# Ind_current_sensor.net
KiCad netlist of a schematic drawn in Altium Designer
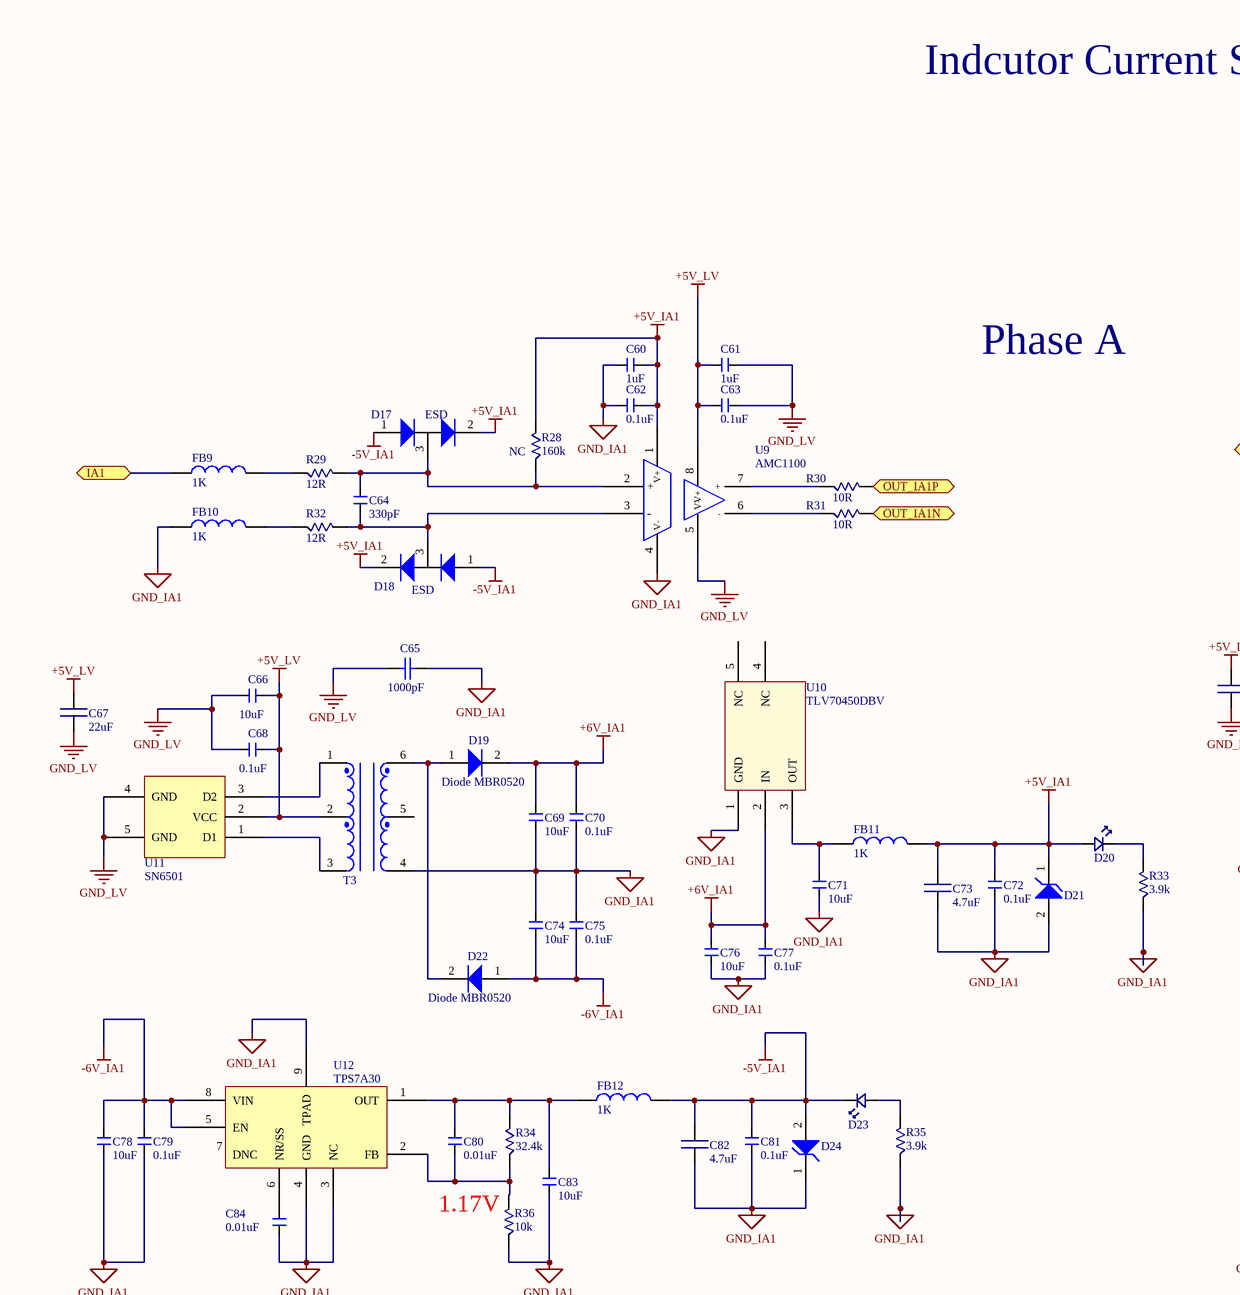
[diagram p0: Ind_current_sensor.SchDoc, top left]
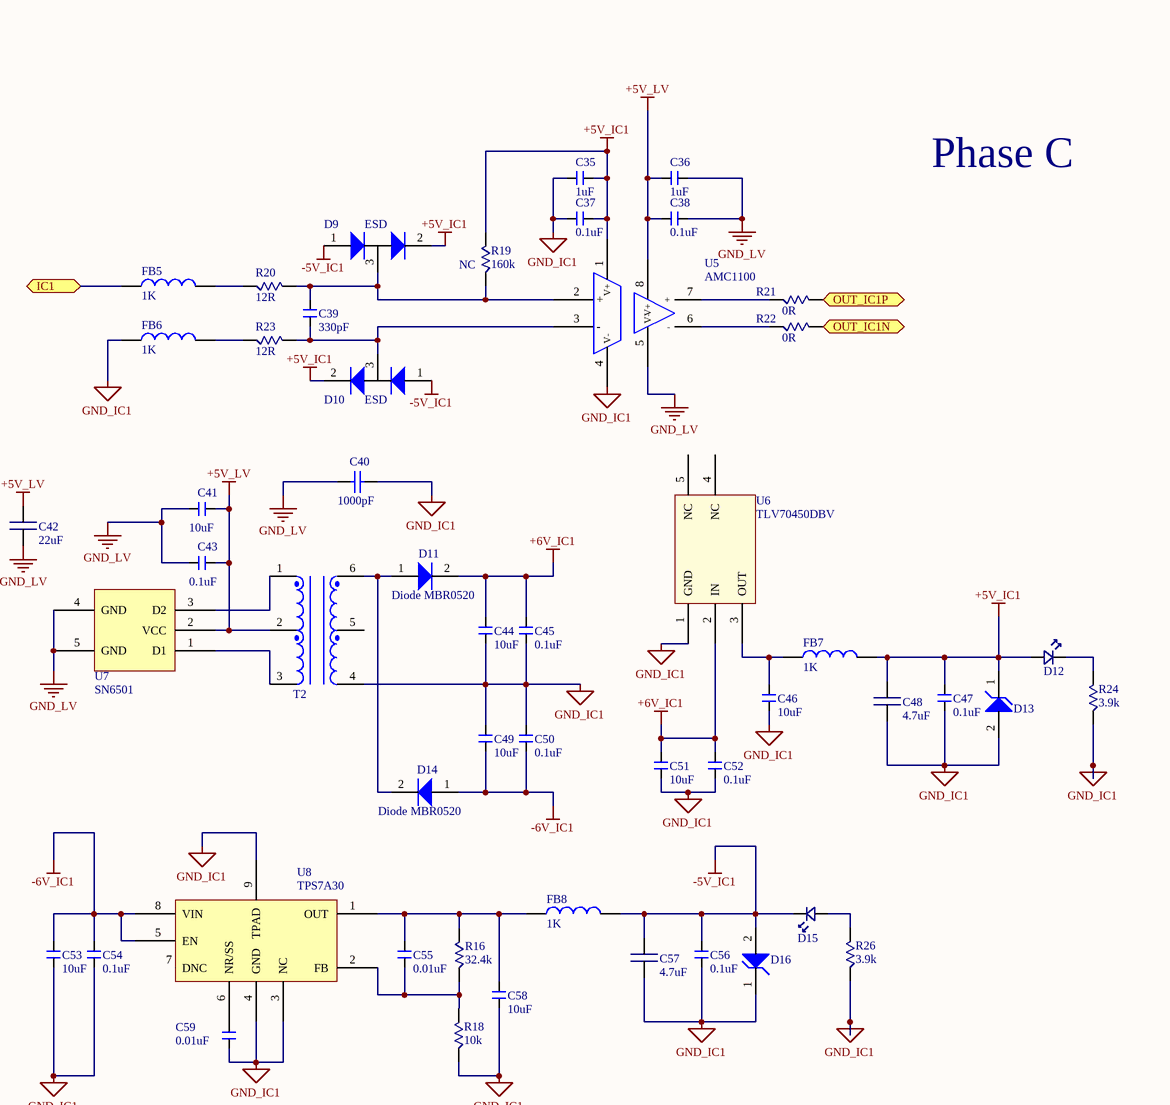
[diagram p1: Ind_current_sensor.SchDoc, top right]
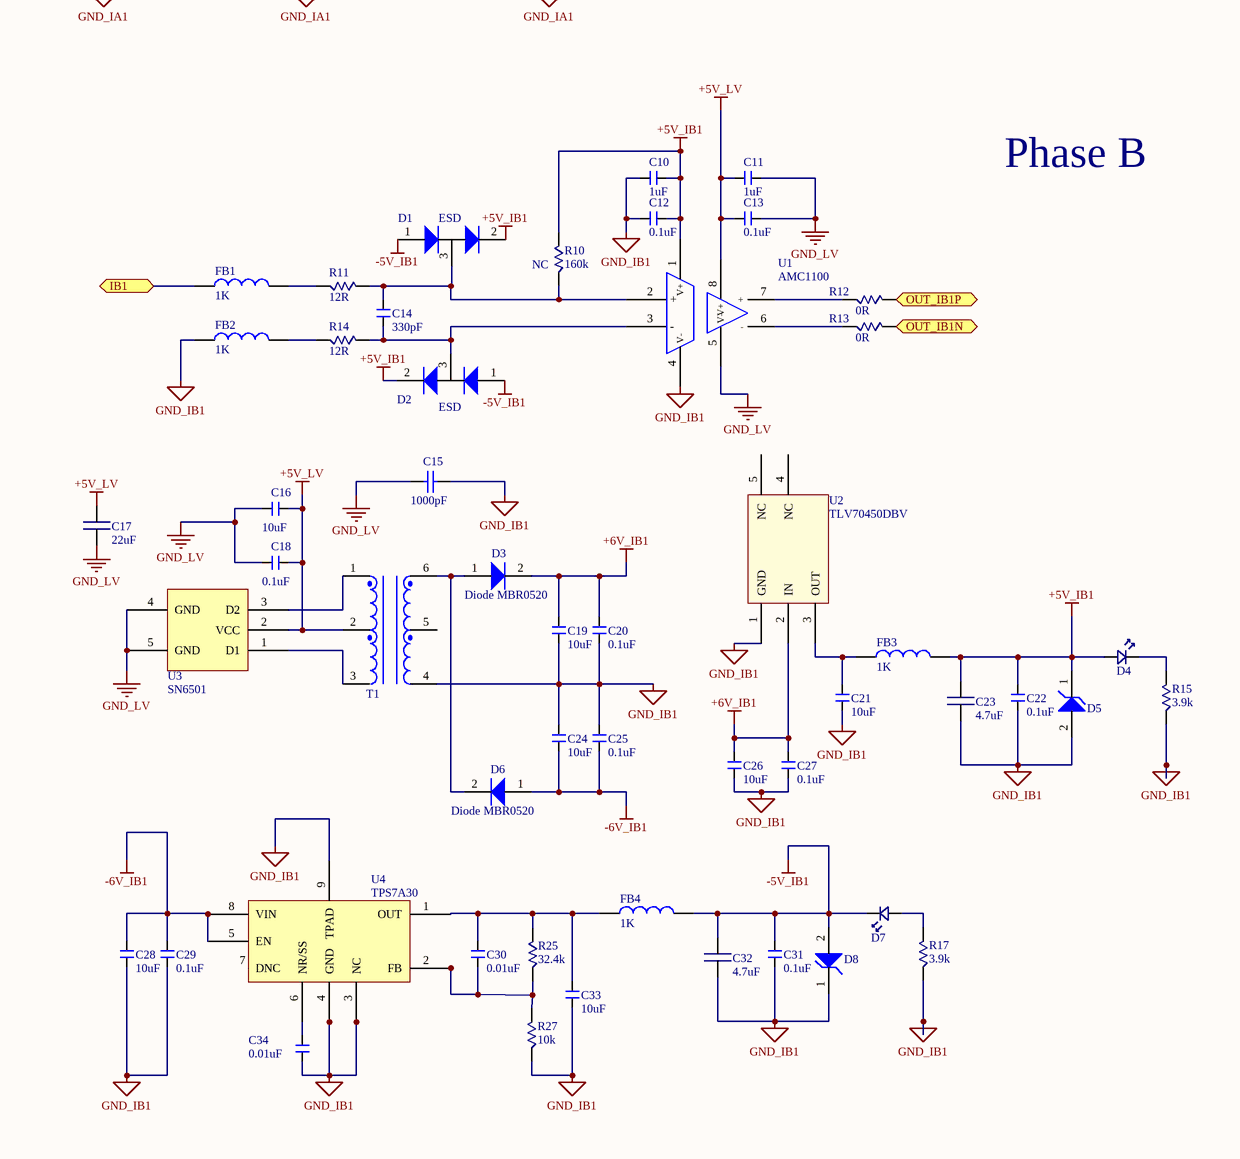
[diagram p2: Ind_current_sensor.SchDoc, bottom left]
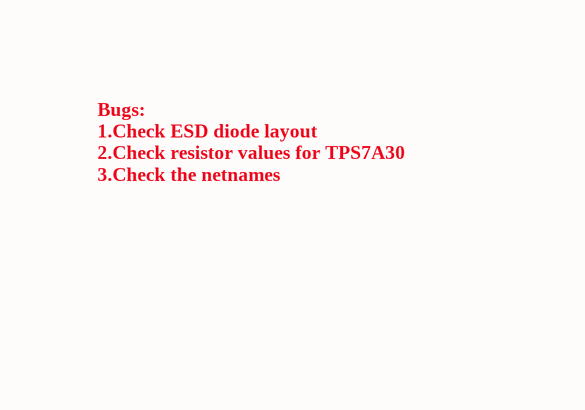
[diagram p3: Ind_current_sensor.SchDoc, bottom right]

(export (version "E")
  (design (tool "Eeschema 10.0.6"))
  (components
    (comp (ref "C10")
      (value "1uF")
      (footprint "0603 (1608 Metric)")
      (description "CAP CER 1UF 50V X5R 0603")
      (fields (field (name "PART") "1276-1860-1-ND") (field (name "Comment") "Cap 0603_new"))
      (libsource (lib "Library_Microgrid") (part "Cap 0603_new"))
    )
    (comp (ref "C11")
      (value "1uF")
      (footprint "0603 (1608 Metric)")
      (description "CAP CER 1UF 50V X5R 0603")
      (fields (field (name "PART") "1276-1860-1-ND") (field (name "Comment") "Cap 0603_new"))
      (libsource (lib "Library_Microgrid") (part "Cap 0603_new"))
    )
    (comp (ref "C12")
      (value "0.1uF")
      (footprint "0603 (1608 Metric)")
      (description "CAP CER 0.1UF 50V Y5V 0603")
      (fields (field (name "PART") "311-1343-6-ND") (field (name "Comment") "Cap 0603_new"))
      (libsource (lib "Library_Microgrid") (part "Cap 0603_new"))
    )
    (comp (ref "C13")
      (value "0.1uF")
      (footprint "0603 (1608 Metric)")
      (description "CAP CER 0.1UF 50V Y5V 0603")
      (fields (field (name "PART") "311-1343-6-ND") (field (name "Comment") "Cap 0603_new"))
      (libsource (lib "Library_Microgrid") (part "Cap 0603_new"))
    )
    (comp (ref "C14")
      (value "330pF")
      (footprint "0603 (1608 Metric)")
      (description "CAP CER 330PF 50V C0G 0603")
      (fields (field (name "PART") "445-7033-2-ND") (field (name "Comment") "Cap 0603_new"))
      (libsource (lib "Library_Microgrid") (part "Cap 0603_new"))
    )
    (comp (ref "C15")
      (value "1000pF")
      (footprint "RAD-0.3")
      (description "CAP CER 1000PF 1KV Y5P RADIAL")
      (fields
        (field (name "PART") "1251PH-ND")
        (field (name "Comment") "Cap TH")
        (field (name "PUBLISHER") "Altium Limited")
      )
      (libsource (lib "Miscellaneous Devices") (part "Cap"))
    )
    (comp (ref "C16")
      (value "10uF")
      (footprint "0603 (1608 Metric)")
      (description "CAP CER 10UF 35V X5R 0805")
      (fields (field (name "PART") "490-10515-1-ND") (field (name "Comment") "Cap 0603_new"))
      (libsource (lib "Library_Microgrid") (part "Cap 0603_new"))
    )
    (comp (ref "C17")
      (value "22uF")
      (footprint "0805 (2012 metric)")
      (description "CAP CER 22UF 35V X5R 0805")
      (fields (field (name "PART") "445-14428-1-ND") (field (name "Comment") "Cap 0805"))
      (libsource (lib "Library_Microgrid") (part "Cap 0805"))
    )
    (comp (ref "C18")
      (value "0.1uF")
      (footprint "0603 (1608 Metric)")
      (description "CAP CER 0.1UF 50V Y5V 0603")
      (fields (field (name "PART") "311-1343-6-ND") (field (name "Comment") "Cap 0603_new"))
      (libsource (lib "Library_Microgrid") (part "Cap 0603_new"))
    )
    (comp (ref "C19")
      (value "10uF")
      (footprint "0603 (1608 Metric)")
      (description "CAP CER 10UF 35V X5R 0805")
      (fields (field (name "PART") "490-10515-1-ND") (field (name "Comment") "Cap 0603_new"))
      (libsource (lib "Library_Microgrid") (part "Cap 0603_new"))
    )
    (comp (ref "C20")
      (value "0.1uF")
      (footprint "0603 (1608 Metric)")
      (description "CAP CER 0.1UF 50V Y5V 0603")
      (fields (field (name "PART") "311-1343-6-ND") (field (name "Comment") "Cap 0603_new"))
      (libsource (lib "Library_Microgrid") (part "Cap 0603_new"))
    )
    (comp (ref "C21")
      (value "10uF")
      (footprint "0603 (1608 Metric)")
      (description "CAP CER 10UF 35V X5R 0805")
      (fields (field (name "PART") "490-10515-1-ND") (field (name "Comment") "Cap 0603_new"))
      (libsource (lib "Library_Microgrid") (part "Cap 0603_new"))
    )
    (comp (ref "C22")
      (value "0.1uF")
      (footprint "0603 (1608 Metric)")
      (description "CAP CER 0.1UF 50V Y5V 0603")
      (fields (field (name "PART") "311-1343-6-ND") (field (name "Comment") "Cap 0603_new"))
      (libsource (lib "Library_Microgrid") (part "Cap 0603_new"))
    )
    (comp (ref "C23")
      (value "4.7uF")
      (footprint "0805 (2012 metric)")
      (description "CAP CER 4.7UF 50V X5R 0805")
      (fields (field (name "PART") "445-5980-1-ND") (field (name "Comment") "Cap 0805"))
      (libsource (lib "Library_Microgrid") (part "Cap 0805"))
    )
    (comp (ref "C24")
      (value "10uF")
      (footprint "0603 (1608 Metric)")
      (description "CAP CER 10UF 35V X5R 0805")
      (fields (field (name "PART") "490-10515-1-ND") (field (name "Comment") "Cap 0603_new"))
      (libsource (lib "Library_Microgrid") (part "Cap 0603_new"))
    )
    (comp (ref "C25")
      (value "0.1uF")
      (footprint "0603 (1608 Metric)")
      (description "CAP CER 0.1UF 50V Y5V 0603")
      (fields (field (name "PART") "311-1343-6-ND") (field (name "Comment") "Cap 0603_new"))
      (libsource (lib "Library_Microgrid") (part "Cap 0603_new"))
    )
    (comp (ref "C26")
      (value "10uF")
      (footprint "0603 (1608 Metric)")
      (description "CAP CER 10UF 35V X5R 0805")
      (fields (field (name "PART") "490-10515-1-ND") (field (name "Comment") "Cap 0603_new"))
      (libsource (lib "Library_Microgrid") (part "Cap 0603_new"))
    )
    (comp (ref "C27")
      (value "0.1uF")
      (footprint "0603 (1608 Metric)")
      (description "CAP CER 0.1UF 50V Y5V 0603")
      (fields (field (name "PART") "311-1343-6-ND") (field (name "Comment") "Cap 0603_new"))
      (libsource (lib "Library_Microgrid") (part "Cap 0603_new"))
    )
    (comp (ref "C28")
      (value "10uF")
      (footprint "0603 (1608 Metric)")
      (description "CAP CER 10UF 35V X5R 0805")
      (fields (field (name "PART") "490-10515-1-ND") (field (name "Comment") "Cap 0603_new"))
      (libsource (lib "Library_Microgrid") (part "Cap 0603_new"))
    )
    (comp (ref "C29")
      (value "0.1uF")
      (footprint "0603 (1608 Metric)")
      (description "CAP CER 0.1UF 50V Y5V 0603")
      (fields (field (name "PART") "311-1343-6-ND") (field (name "Comment") "Cap 0603_new"))
      (libsource (lib "Library_Microgrid") (part "Cap 0603_new"))
    )
    (comp (ref "C30")
      (value "0.01uF")
      (footprint "0603 (1608 Metric)")
      (description "CAP CER 10000PF 100V X7R 0603")
      (fields (field (name "PART") "478-7418-1-ND") (field (name "Comment") "Cap 0603_new"))
      (libsource (lib "Library_Microgrid") (part "Cap 0603_new"))
    )
    (comp (ref "C31")
      (value "0.1uF")
      (footprint "0603 (1608 Metric)")
      (description "CAP CER 0.1UF 50V Y5V 0603")
      (fields (field (name "PART") "311-1343-6-ND") (field (name "Comment") "Cap 0603_new"))
      (libsource (lib "Library_Microgrid") (part "Cap 0603_new"))
    )
    (comp (ref "C32")
      (value "4.7uF")
      (footprint "0805 (2012 metric)")
      (description "CAP CER 4.7UF 50V X5R 0805")
      (fields (field (name "PART") "445-5980-1-ND") (field (name "Comment") "Cap 0805"))
      (libsource (lib "Library_Microgrid") (part "Cap 0805"))
    )
    (comp (ref "C33")
      (value "10uF")
      (footprint "0603 (1608 Metric)")
      (description "CAP CER 10UF 35V X5R 0805")
      (fields (field (name "PART") "490-10515-1-ND") (field (name "Comment") "Cap 0603_new"))
      (libsource (lib "Library_Microgrid") (part "Cap 0603_new"))
    )
    (comp (ref "C34")
      (value "0.01uF")
      (footprint "0603 (1608 Metric)")
      (description "CAP CER 10000PF 100V X7R 0603")
      (fields (field (name "PART") "478-7418-1-ND") (field (name "Comment") "Cap 0603_new"))
      (libsource (lib "Library_Microgrid") (part "Cap 0603_new"))
    )
    (comp (ref "C35")
      (value "1uF")
      (footprint "0603 (1608 Metric)")
      (description "CAP CER 1UF 50V X5R 0603")
      (fields (field (name "PART") "1276-1860-1-ND") (field (name "Comment") "Cap 0603_new"))
      (libsource (lib "Library_Microgrid") (part "Cap 0603_new"))
    )
    (comp (ref "C36")
      (value "1uF")
      (footprint "0603 (1608 Metric)")
      (description "CAP CER 1UF 50V X5R 0603")
      (fields (field (name "PART") "1276-1860-1-ND") (field (name "Comment") "Cap 0603_new"))
      (libsource (lib "Library_Microgrid") (part "Cap 0603_new"))
    )
    (comp (ref "C37")
      (value "0.1uF")
      (footprint "0603 (1608 Metric)")
      (description "CAP CER 0.1UF 50V Y5V 0603")
      (fields (field (name "PART") "311-1343-6-ND") (field (name "Comment") "Cap 0603_new"))
      (libsource (lib "Library_Microgrid") (part "Cap 0603_new"))
    )
    (comp (ref "C38")
      (value "0.1uF")
      (footprint "0603 (1608 Metric)")
      (description "CAP CER 0.1UF 50V Y5V 0603")
      (fields (field (name "PART") "311-1343-6-ND") (field (name "Comment") "Cap 0603_new"))
      (libsource (lib "Library_Microgrid") (part "Cap 0603_new"))
    )
    (comp (ref "C39")
      (value "330pF")
      (footprint "0603 (1608 Metric)")
      (description "CAP CER 330PF 50V C0G 0603")
      (fields (field (name "PART") "445-7033-2-ND") (field (name "Comment") "Cap 0603_new"))
      (libsource (lib "Library_Microgrid") (part "Cap 0603_new"))
    )
    (comp (ref "C40")
      (value "1000pF")
      (footprint "RAD-0.3")
      (description "CAP CER 1000PF 1KV Y5P RADIAL")
      (fields
        (field (name "PART") "1251PH-ND")
        (field (name "Comment") "Cap TH")
        (field (name "PUBLISHER") "Altium Limited")
      )
      (libsource (lib "Miscellaneous Devices") (part "Cap"))
    )
    (comp (ref "C41")
      (value "10uF")
      (footprint "0603 (1608 Metric)")
      (description "CAP CER 10UF 35V X5R 0805")
      (fields (field (name "PART") "490-10515-1-ND") (field (name "Comment") "Cap 0603_new"))
      (libsource (lib "Library_Microgrid") (part "Cap 0603_new"))
    )
    (comp (ref "C42")
      (value "22uF")
      (footprint "0805 (2012 metric)")
      (description "CAP CER 22UF 35V X5R 0805")
      (fields (field (name "PART") "445-14428-1-ND") (field (name "Comment") "Cap 0805"))
      (libsource (lib "Library_Microgrid") (part "Cap 0805"))
    )
    (comp (ref "C43")
      (value "0.1uF")
      (footprint "0603 (1608 Metric)")
      (description "CAP CER 0.1UF 50V Y5V 0603")
      (fields (field (name "PART") "311-1343-6-ND") (field (name "Comment") "Cap 0603_new"))
      (libsource (lib "Library_Microgrid") (part "Cap 0603_new"))
    )
    (comp (ref "C44")
      (value "10uF")
      (footprint "0603 (1608 Metric)")
      (description "CAP CER 10UF 35V X5R 0805")
      (fields (field (name "PART") "490-10515-1-ND") (field (name "Comment") "Cap 0603_new"))
      (libsource (lib "Library_Microgrid") (part "Cap 0603_new"))
    )
    (comp (ref "C45")
      (value "0.1uF")
      (footprint "0603 (1608 Metric)")
      (description "CAP CER 0.1UF 50V Y5V 0603")
      (fields (field (name "PART") "311-1343-6-ND") (field (name "Comment") "Cap 0603_new"))
      (libsource (lib "Library_Microgrid") (part "Cap 0603_new"))
    )
    (comp (ref "C46")
      (value "10uF")
      (footprint "0603 (1608 Metric)")
      (description "CAP CER 10UF 35V X5R 0805")
      (fields (field (name "PART") "490-10515-1-ND") (field (name "Comment") "Cap 0603_new"))
      (libsource (lib "Library_Microgrid") (part "Cap 0603_new"))
    )
    (comp (ref "C47")
      (value "0.1uF")
      (footprint "0603 (1608 Metric)")
      (description "CAP CER 0.1UF 50V Y5V 0603")
      (fields (field (name "PART") "311-1343-6-ND") (field (name "Comment") "Cap 0603_new"))
      (libsource (lib "Library_Microgrid") (part "Cap 0603_new"))
    )
    (comp (ref "C48")
      (value "4.7uF")
      (footprint "0805 (2012 metric)")
      (description "CAP CER 4.7UF 50V X5R 0805")
      (fields (field (name "PART") "445-5980-1-ND") (field (name "Comment") "Cap 0805"))
      (libsource (lib "Library_Microgrid") (part "Cap 0805"))
    )
    (comp (ref "C49")
      (value "10uF")
      (footprint "0603 (1608 Metric)")
      (description "CAP CER 10UF 35V X5R 0805")
      (fields (field (name "PART") "490-10515-1-ND") (field (name "Comment") "Cap 0603_new"))
      (libsource (lib "Library_Microgrid") (part "Cap 0603_new"))
    )
    (comp (ref "C50")
      (value "0.1uF")
      (footprint "0603 (1608 Metric)")
      (description "CAP CER 0.1UF 50V Y5V 0603")
      (fields (field (name "PART") "311-1343-6-ND") (field (name "Comment") "Cap 0603_new"))
      (libsource (lib "Library_Microgrid") (part "Cap 0603_new"))
    )
    (comp (ref "C51")
      (value "10uF")
      (footprint "0603 (1608 Metric)")
      (description "CAP CER 10UF 35V X5R 0805")
      (fields (field (name "PART") "490-10515-1-ND") (field (name "Comment") "Cap 0603_new"))
      (libsource (lib "Library_Microgrid") (part "Cap 0603_new"))
    )
    (comp (ref "C52")
      (value "0.1uF")
      (footprint "0603 (1608 Metric)")
      (description "CAP CER 0.1UF 50V Y5V 0603")
      (fields (field (name "PART") "311-1343-6-ND") (field (name "Comment") "Cap 0603_new"))
      (libsource (lib "Library_Microgrid") (part "Cap 0603_new"))
    )
    (comp (ref "C53")
      (value "10uF")
      (footprint "0603 (1608 Metric)")
      (description "CAP CER 10UF 35V X5R 0805")
      (fields (field (name "PART") "490-10515-1-ND") (field (name "Comment") "Cap 0603_new"))
      (libsource (lib "Library_Microgrid") (part "Cap 0603_new"))
    )
    (comp (ref "C54")
      (value "0.1uF")
      (footprint "0603 (1608 Metric)")
      (description "CAP CER 0.1UF 50V Y5V 0603")
      (fields (field (name "PART") "311-1343-6-ND") (field (name "Comment") "Cap 0603_new"))
      (libsource (lib "Library_Microgrid") (part "Cap 0603_new"))
    )
    (comp (ref "C55")
      (value "0.01uF")
      (footprint "0603 (1608 Metric)")
      (description "CAP CER 10000PF 100V X7R 0603")
      (fields (field (name "PART") "478-7418-1-ND") (field (name "Comment") "Cap 0603_new"))
      (libsource (lib "Library_Microgrid") (part "Cap 0603_new"))
    )
    (comp (ref "C56")
      (value "0.1uF")
      (footprint "0603 (1608 Metric)")
      (description "CAP CER 0.1UF 50V Y5V 0603")
      (fields (field (name "PART") "311-1343-6-ND") (field (name "Comment") "Cap 0603_new"))
      (libsource (lib "Library_Microgrid") (part "Cap 0603_new"))
    )
    (comp (ref "C57")
      (value "4.7uF")
      (footprint "0805 (2012 metric)")
      (description "CAP CER 4.7UF 50V X5R 0805")
      (fields (field (name "PART") "445-5980-1-ND") (field (name "Comment") "Cap 0805"))
      (libsource (lib "Library_Microgrid") (part "Cap 0805"))
    )
    (comp (ref "C58")
      (value "10uF")
      (footprint "0603 (1608 Metric)")
      (description "CAP CER 10UF 35V X5R 0805")
      (fields (field (name "PART") "490-10515-1-ND") (field (name "Comment") "Cap 0603_new"))
      (libsource (lib "Library_Microgrid") (part "Cap 0603_new"))
    )
    (comp (ref "C59")
      (value "0.01uF")
      (footprint "0603 (1608 Metric)")
      (description "CAP CER 10000PF 100V X7R 0603")
      (fields (field (name "PART") "478-7418-1-ND") (field (name "Comment") "Cap 0603_new"))
      (libsource (lib "Library_Microgrid") (part "Cap 0603_new"))
    )
    (comp (ref "C60")
      (value "1uF")
      (footprint "0603 (1608 Metric)")
      (description "CAP CER 1UF 50V X5R 0603")
      (fields (field (name "PART") "1276-1860-1-ND") (field (name "Comment") "Cap 0603_new"))
      (libsource (lib "Library_Microgrid") (part "Cap 0603_new"))
    )
    (comp (ref "C61")
      (value "1uF")
      (footprint "0603 (1608 Metric)")
      (description "CAP CER 1UF 50V X5R 0603")
      (fields (field (name "PART") "1276-1860-1-ND") (field (name "Comment") "Cap 0603_new"))
      (libsource (lib "Library_Microgrid") (part "Cap 0603_new"))
    )
    (comp (ref "C62")
      (value "0.1uF")
      (footprint "0603 (1608 Metric)")
      (description "CAP CER 0.1UF 50V Y5V 0603")
      (fields (field (name "PART") "311-1343-6-ND") (field (name "Comment") "Cap 0603_new"))
      (libsource (lib "Library_Microgrid") (part "Cap 0603_new"))
    )
    (comp (ref "C63")
      (value "0.1uF")
      (footprint "0603 (1608 Metric)")
      (description "CAP CER 0.1UF 50V Y5V 0603")
      (fields (field (name "PART") "311-1343-6-ND") (field (name "Comment") "Cap 0603_new"))
      (libsource (lib "Library_Microgrid") (part "Cap 0603_new"))
    )
    (comp (ref "C64")
      (value "330pF")
      (footprint "0603 (1608 Metric)")
      (description "CAP CER 330PF 50V C0G 0603")
      (fields (field (name "PART") "445-7033-2-ND") (field (name "Comment") "Cap 0603_new"))
      (libsource (lib "Library_Microgrid") (part "Cap 0603_new"))
    )
    (comp (ref "C65")
      (value "1000pF")
      (footprint "RAD-0.3")
      (description "CAP CER 1000PF 1KV Y5P RADIAL")
      (fields
        (field (name "PART") "1251PH-ND")
        (field (name "Comment") "Cap TH")
        (field (name "PUBLISHER") "Altium Limited")
      )
      (libsource (lib "Miscellaneous Devices") (part "Cap"))
    )
    (comp (ref "C66")
      (value "10uF")
      (footprint "0603 (1608 Metric)")
      (description "CAP CER 10UF 35V X5R 0805")
      (fields (field (name "PART") "490-10515-1-ND") (field (name "Comment") "Cap 0603_new"))
      (libsource (lib "Library_Microgrid") (part "Cap 0603_new"))
    )
    (comp (ref "C67")
      (value "22uF")
      (footprint "0805 (2012 metric)")
      (description "CAP CER 22UF 35V X5R 0805")
      (fields (field (name "PART") "445-14428-1-ND") (field (name "Comment") "Cap 0805"))
      (libsource (lib "Library_Microgrid") (part "Cap 0805"))
    )
    (comp (ref "C68")
      (value "0.1uF")
      (footprint "0603 (1608 Metric)")
      (description "CAP CER 0.1UF 50V Y5V 0603")
      (fields (field (name "PART") "311-1343-6-ND") (field (name "Comment") "Cap 0603_new"))
      (libsource (lib "Library_Microgrid") (part "Cap 0603_new"))
    )
    (comp (ref "C69")
      (value "10uF")
      (footprint "0603 (1608 Metric)")
      (description "CAP CER 10UF 35V X5R 0805")
      (fields (field (name "PART") "490-10515-1-ND") (field (name "Comment") "Cap 0603_new"))
      (libsource (lib "Library_Microgrid") (part "Cap 0603_new"))
    )
    (comp (ref "C70")
      (value "0.1uF")
      (footprint "0603 (1608 Metric)")
      (description "CAP CER 0.1UF 50V Y5V 0603")
      (fields (field (name "PART") "311-1343-6-ND") (field (name "Comment") "Cap 0603_new"))
      (libsource (lib "Library_Microgrid") (part "Cap 0603_new"))
    )
    (comp (ref "C71")
      (value "10uF")
      (footprint "0603 (1608 Metric)")
      (description "CAP CER 10UF 35V X5R 0805")
      (fields (field (name "PART") "490-10515-1-ND") (field (name "Comment") "Cap 0603_new"))
      (libsource (lib "Library_Microgrid") (part "Cap 0603_new"))
    )
    (comp (ref "C72")
      (value "0.1uF")
      (footprint "0603 (1608 Metric)")
      (description "CAP CER 0.1UF 50V Y5V 0603")
      (fields (field (name "PART") "311-1343-6-ND") (field (name "Comment") "Cap 0603_new"))
      (libsource (lib "Library_Microgrid") (part "Cap 0603_new"))
    )
    (comp (ref "C73")
      (value "4.7uF")
      (footprint "0805 (2012 metric)")
      (description "CAP CER 4.7UF 50V X5R 0805")
      (fields (field (name "PART") "445-5980-1-ND") (field (name "Comment") "Cap 0805"))
      (libsource (lib "Library_Microgrid") (part "Cap 0805"))
    )
    (comp (ref "C74")
      (value "10uF")
      (footprint "0603 (1608 Metric)")
      (description "CAP CER 10UF 35V X5R 0805")
      (fields (field (name "PART") "490-10515-1-ND") (field (name "Comment") "Cap 0603_new"))
      (libsource (lib "Library_Microgrid") (part "Cap 0603_new"))
    )
    (comp (ref "C75")
      (value "0.1uF")
      (footprint "0603 (1608 Metric)")
      (description "CAP CER 0.1UF 50V Y5V 0603")
      (fields (field (name "PART") "311-1343-6-ND") (field (name "Comment") "Cap 0603_new"))
      (libsource (lib "Library_Microgrid") (part "Cap 0603_new"))
    )
    (comp (ref "C76")
      (value "10uF")
      (footprint "0603 (1608 Metric)")
      (description "CAP CER 10UF 35V X5R 0805")
      (fields (field (name "PART") "490-10515-1-ND") (field (name "Comment") "Cap 0603_new"))
      (libsource (lib "Library_Microgrid") (part "Cap 0603_new"))
    )
    (comp (ref "C77")
      (value "0.1uF")
      (footprint "0603 (1608 Metric)")
      (description "CAP CER 0.1UF 50V Y5V 0603")
      (fields (field (name "PART") "311-1343-6-ND") (field (name "Comment") "Cap 0603_new"))
      (libsource (lib "Library_Microgrid") (part "Cap 0603_new"))
    )
    (comp (ref "C78")
      (value "10uF")
      (footprint "0603 (1608 Metric)")
      (description "CAP CER 10UF 35V X5R 0805")
      (fields (field (name "PART") "490-10515-1-ND") (field (name "Comment") "Cap 0603_new"))
      (libsource (lib "Library_Microgrid") (part "Cap 0603_new"))
    )
    (comp (ref "C79")
      (value "0.1uF")
      (footprint "0603 (1608 Metric)")
      (description "CAP CER 0.1UF 50V Y5V 0603")
      (fields (field (name "PART") "311-1343-6-ND") (field (name "Comment") "Cap 0603_new"))
      (libsource (lib "Library_Microgrid") (part "Cap 0603_new"))
    )
    (comp (ref "C80")
      (value "0.01uF")
      (footprint "0603 (1608 Metric)")
      (description "CAP CER 10000PF 100V X7R 0603")
      (fields (field (name "PART") "478-7418-1-ND") (field (name "Comment") "Cap 0603_new"))
      (libsource (lib "Library_Microgrid") (part "Cap 0603_new"))
    )
    (comp (ref "C81")
      (value "0.1uF")
      (footprint "0603 (1608 Metric)")
      (description "CAP CER 0.1UF 50V Y5V 0603")
      (fields (field (name "PART") "311-1343-6-ND") (field (name "Comment") "Cap 0603_new"))
      (libsource (lib "Library_Microgrid") (part "Cap 0603_new"))
    )
    (comp (ref "C82")
      (value "4.7uF")
      (footprint "0805 (2012 metric)")
      (description "CAP CER 4.7UF 50V X5R 0805")
      (fields (field (name "PART") "445-5980-1-ND") (field (name "Comment") "Cap 0805"))
      (libsource (lib "Library_Microgrid") (part "Cap 0805"))
    )
    (comp (ref "C83")
      (value "10uF")
      (footprint "0603 (1608 Metric)")
      (description "CAP CER 10UF 35V X5R 0805")
      (fields (field (name "PART") "490-10515-1-ND") (field (name "Comment") "Cap 0603_new"))
      (libsource (lib "Library_Microgrid") (part "Cap 0603_new"))
    )
    (comp (ref "C84")
      (value "0.01uF")
      (footprint "0603 (1608 Metric)")
      (description "CAP CER 10000PF 100V X7R 0603")
      (fields (field (name "PART") "478-7418-1-ND") (field (name "Comment") "Cap 0603_new"))
      (libsource (lib "Library_Microgrid") (part "Cap 0603_new"))
    )
    (comp (ref "D1")
      (value "ESD")
      (footprint "SOT323_ESD")
      (description "TVS DIODE")
      (fields (field (name "PART") "ESD1P0RFWH6327XTSA1CT") (field (name "Comment") "TVS - Diodes"))
      (libsource (lib "Library_Microgrid") (part "Diode_ESD"))
    )
    (comp (ref "D2")
      (value "ESD")
      (footprint "SOT323_ESD")
      (description "TVS DIODE")
      (fields (field (name "PART") "ESD1P0RFWH6327XTSA1CT") (field (name "Comment") "TVS - Diodes"))
      (libsource (lib "Library_Microgrid") (part "Diode_ESD"))
    )
    (comp (ref "D3")
      (value "Diode MBR0520")
      (footprint "SOD-123")
      (description "DIODE SCHOTTKY 20V 500MA SOD123")
      (fields (field (name "PART") "MBR0520LT1GOSCT-ND"))
      (libsource (lib "Library_Microgrid") (part "Diode MBR0520"))
    )
    (comp (ref "D4")
      (value "LED")
      (footprint "0805 (2012 Metric) Diode")
      (description "LED 0805")
      (libsource (lib "Library_Microgrid") (part "LED"))
    )
    (comp (ref "D5")
      (value "Diode Zener POWERDI123")
      (footprint "POWERDI")
      (description "DIODE ZENER POWERDI123")
      (fields (field (name "PART") "DFLZ6V2DICT-ND"))
      (libsource (lib "Library_Microgrid") (part "Diode Zener POWERDI123"))
    )
    (comp (ref "D6")
      (value "Diode MBR0520")
      (footprint "SOD-123")
      (description "DIODE SCHOTTKY 20V 500MA SOD123")
      (fields (field (name "PART") "MBR0520LT1GOSCT-ND"))
      (libsource (lib "Library_Microgrid") (part "Diode MBR0520"))
    )
    (comp (ref "D7")
      (value "LED")
      (footprint "0805 (2012 Metric) Diode")
      (description "LED 0805")
      (libsource (lib "Library_Microgrid") (part "LED"))
    )
    (comp (ref "D8")
      (value "Diode Zener POWERDI123")
      (footprint "POWERDI")
      (description "DIODE ZENER POWERDI123")
      (fields (field (name "PART") "DFLZ6V2DICT-ND"))
      (libsource (lib "Library_Microgrid") (part "Diode Zener POWERDI123"))
    )
    (comp (ref "D9")
      (value "ESD")
      (footprint "SOT323_ESD")
      (description "TVS DIODE")
      (fields (field (name "PART") "ESD1P0RFWH6327XTSA1CT") (field (name "Comment") "TVS - Diodes"))
      (libsource (lib "Library_Microgrid") (part "Diode_ESD"))
    )
    (comp (ref "D10")
      (value "ESD")
      (footprint "SOT323_ESD")
      (description "TVS DIODE")
      (fields (field (name "PART") "ESD1P0RFWH6327XTSA1CT") (field (name "Comment") "TVS - Diodes"))
      (libsource (lib "Library_Microgrid") (part "Diode_ESD"))
    )
    (comp (ref "D11")
      (value "Diode MBR0520")
      (footprint "SOD-123")
      (description "DIODE SCHOTTKY 20V 500MA SOD123")
      (fields (field (name "PART") "MBR0520LT1GOSCT-ND"))
      (libsource (lib "Library_Microgrid") (part "Diode MBR0520"))
    )
    (comp (ref "D12")
      (value "LED")
      (footprint "0805 (2012 Metric) Diode")
      (description "LED 0805")
      (libsource (lib "Library_Microgrid") (part "LED"))
    )
    (comp (ref "D13")
      (value "Diode Zener POWERDI123")
      (footprint "POWERDI")
      (description "DIODE ZENER POWERDI123")
      (fields (field (name "PART") "DFLZ6V2DICT-ND"))
      (libsource (lib "Library_Microgrid") (part "Diode Zener POWERDI123"))
    )
    (comp (ref "D14")
      (value "Diode MBR0520")
      (footprint "SOD-123")
      (description "DIODE SCHOTTKY 20V 500MA SOD123")
      (fields (field (name "PART") "MBR0520LT1GOSCT-ND"))
      (libsource (lib "Library_Microgrid") (part "Diode MBR0520"))
    )
    (comp (ref "D15")
      (value "LED")
      (footprint "0805 (2012 Metric) Diode")
      (description "LED 0805")
      (libsource (lib "Library_Microgrid") (part "LED"))
    )
    (comp (ref "D16")
      (value "Diode Zener POWERDI123")
      (footprint "POWERDI")
      (description "DIODE ZENER POWERDI123")
      (fields (field (name "PART") "DFLZ6V2DICT-ND"))
      (libsource (lib "Library_Microgrid") (part "Diode Zener POWERDI123"))
    )
    (comp (ref "D17")
      (value "ESD")
      (footprint "SOT323_ESD")
      (description "TVS DIODE")
      (fields (field (name "PART") "ESD1P0RFWH6327XTSA1CT") (field (name "Comment") "TVS - Diodes"))
      (libsource (lib "Library_Microgrid") (part "Diode_ESD"))
    )
    (comp (ref "D18")
      (value "ESD")
      (footprint "SOT323_ESD")
      (description "TVS DIODE")
      (fields (field (name "PART") "ESD1P0RFWH6327XTSA1CT") (field (name "Comment") "TVS - Diodes"))
      (libsource (lib "Library_Microgrid") (part "Diode_ESD"))
    )
    (comp (ref "D19")
      (value "Diode MBR0520")
      (footprint "SOD-123")
      (description "DIODE SCHOTTKY 20V 500MA SOD123")
      (fields (field (name "PART") "MBR0520LT1GOSCT-ND"))
      (libsource (lib "Library_Microgrid") (part "Diode MBR0520"))
    )
    (comp (ref "D20")
      (value "LED")
      (footprint "0805 (2012 Metric) Diode")
      (description "LED 0805")
      (libsource (lib "Library_Microgrid") (part "LED"))
    )
    (comp (ref "D21")
      (value "Diode Zener POWERDI123")
      (footprint "POWERDI")
      (description "DIODE ZENER POWERDI123")
      (fields (field (name "PART") "DFLZ6V2DICT-ND"))
      (libsource (lib "Library_Microgrid") (part "Diode Zener POWERDI123"))
    )
    (comp (ref "D22")
      (value "Diode MBR0520")
      (footprint "SOD-123")
      (description "DIODE SCHOTTKY 20V 500MA SOD123")
      (fields (field (name "PART") "MBR0520LT1GOSCT-ND"))
      (libsource (lib "Library_Microgrid") (part "Diode MBR0520"))
    )
    (comp (ref "D23")
      (value "LED")
      (footprint "0805 (2012 Metric) Diode")
      (description "LED 0805")
      (libsource (lib "Library_Microgrid") (part "LED"))
    )
    (comp (ref "D24")
      (value "Diode Zener POWERDI123")
      (footprint "POWERDI")
      (description "DIODE ZENER POWERDI123")
      (fields (field (name "PART") "DFLZ6V2DICT-ND"))
      (libsource (lib "Library_Microgrid") (part "Diode Zener POWERDI123"))
    )
    (comp (ref "FB1")
      (value "1K")
      (footprint "0603 (1608 Metric)")
      (description "FERRITE BEAD 1 KOHM 0603 1LN")
      (fields (field (name "PART") "445-8672-1-ND") (field (name "Comment") "Ferrite bead"))
      (libsource (lib "Library_Microgrid") (part "Ferrite bead"))
    )
    (comp (ref "FB2")
      (value "1K")
      (footprint "0603 (1608 Metric)")
      (description "FERRITE BEAD 1 KOHM 0603 1LN")
      (fields (field (name "PART") "445-8672-1-ND") (field (name "Comment") "Ferrite bead"))
      (libsource (lib "Library_Microgrid") (part "Ferrite bead"))
    )
    (comp (ref "FB3")
      (value "1K")
      (footprint "0603 (1608 Metric)")
      (description "FERRITE BEAD 1 KOHM 0603 1LN")
      (fields (field (name "PART") "445-8672-1-ND") (field (name "Comment") "Ferrite bead"))
      (libsource (lib "Library_Microgrid") (part "Ferrite bead"))
    )
    (comp (ref "FB4")
      (value "1K")
      (footprint "0603 (1608 Metric)")
      (description "FERRITE BEAD 1 KOHM 0603 1LN")
      (fields (field (name "PART") "445-8672-1-ND") (field (name "Comment") "Ferrite bead"))
      (libsource (lib "Library_Microgrid") (part "Ferrite bead"))
    )
    (comp (ref "FB5")
      (value "1K")
      (footprint "0603 (1608 Metric)")
      (description "FERRITE BEAD 1 KOHM 0603 1LN")
      (fields (field (name "PART") "445-8672-1-ND") (field (name "Comment") "Ferrite bead"))
      (libsource (lib "Library_Microgrid") (part "Ferrite bead"))
    )
    (comp (ref "FB6")
      (value "1K")
      (footprint "0603 (1608 Metric)")
      (description "FERRITE BEAD 1 KOHM 0603 1LN")
      (fields (field (name "PART") "445-8672-1-ND") (field (name "Comment") "Ferrite bead"))
      (libsource (lib "Library_Microgrid") (part "Ferrite bead"))
    )
    (comp (ref "FB7")
      (value "1K")
      (footprint "0603 (1608 Metric)")
      (description "FERRITE BEAD 1 KOHM 0603 1LN")
      (fields (field (name "PART") "445-8672-1-ND") (field (name "Comment") "Ferrite bead"))
      (libsource (lib "Library_Microgrid") (part "Ferrite bead"))
    )
    (comp (ref "FB8")
      (value "1K")
      (footprint "0603 (1608 Metric)")
      (description "FERRITE BEAD 1 KOHM 0603 1LN")
      (fields (field (name "PART") "445-8672-1-ND") (field (name "Comment") "Ferrite bead"))
      (libsource (lib "Library_Microgrid") (part "Ferrite bead"))
    )
    (comp (ref "FB9")
      (value "1K")
      (footprint "0603 (1608 Metric)")
      (description "FERRITE BEAD 1 KOHM 0603 1LN")
      (fields (field (name "PART") "445-8672-1-ND") (field (name "Comment") "Ferrite bead"))
      (libsource (lib "Library_Microgrid") (part "Ferrite bead"))
    )
    (comp (ref "FB10")
      (value "1K")
      (footprint "0603 (1608 Metric)")
      (description "FERRITE BEAD 1 KOHM 0603 1LN")
      (fields (field (name "PART") "445-8672-1-ND") (field (name "Comment") "Ferrite bead"))
      (libsource (lib "Library_Microgrid") (part "Ferrite bead"))
    )
    (comp (ref "FB11")
      (value "1K")
      (footprint "0603 (1608 Metric)")
      (description "FERRITE BEAD 1 KOHM 0603 1LN")
      (fields (field (name "PART") "445-8672-1-ND") (field (name "Comment") "Ferrite bead"))
      (libsource (lib "Library_Microgrid") (part "Ferrite bead"))
    )
    (comp (ref "FB12")
      (value "1K")
      (footprint "0603 (1608 Metric)")
      (description "FERRITE BEAD 1 KOHM 0603 1LN")
      (fields (field (name "PART") "445-8672-1-ND") (field (name "Comment") "Ferrite bead"))
      (libsource (lib "Library_Microgrid") (part "Ferrite bead"))
    )
    (comp (ref "R10")
      (value "NC")
      (footprint "0603 (1608 Metric)")
      (description "Resistor 0603")
      (fields (field (name "ALTIUM_VALUE") "160k"))
      (libsource (lib "Library_Microgrid") (part "Resistor 0603"))
    )
    (comp (ref "R11")
      (value "12R")
      (footprint "1206")
      (description "12 Ohm ±0.5% 0.25W, 1/4W Chip Resistor 1206")
      (fields (field (name "PART") "311-2961-1-ND") (field (name "Comment") "Resistor 1206"))
      (libsource (lib "Library_Microgrid") (part "Resistor 1206"))
    )
    (comp (ref "R12")
      (value "0R")
      (footprint "0603 (1608 Metric)")
      (description "RES SMD 10 OHM 0.05% 1/10W 0603")
      (fields (field (name "PART") "RNCF0603AKT10R0CT-ND") (field (name "Comment") "Resistor 0603"))
      (libsource (lib "Library_Microgrid") (part "Resistor 0603"))
    )
    (comp (ref "R13")
      (value "0R")
      (footprint "0603 (1608 Metric)")
      (description "RES SMD 10 OHM 0.05% 1/10W 0603")
      (fields (field (name "PART") "RNCF0603AKT10R0CT-ND") (field (name "Comment") "Resistor 0603"))
      (libsource (lib "Library_Microgrid") (part "Resistor 0603"))
    )
    (comp (ref "R14")
      (value "12R")
      (footprint "1206")
      (description "12 Ohm ±0.5% 0.25W, 1/4W Chip Resistor 1206")
      (fields (field (name "PART") "311-2961-1-ND") (field (name "Comment") "Resistor 1206"))
      (libsource (lib "Library_Microgrid") (part "Resistor 1206"))
    )
    (comp (ref "R15")
      (value "3.9k")
      (footprint "0603 (1608 Metric)")
      (description "RES SMD 3.9K OHM 5% 1/10W 0603")
      (fields (field (name "PART") "541-3.9KGCT-ND") (field (name "Comment") "Resistor 0603"))
      (libsource (lib "Library_Microgrid") (part "Resistor 0603"))
    )
    (comp (ref "R16")
      (value "32.4k")
      (footprint "0603 (1608 Metric)")
      (description "RES SMD 32.4KOHM 0.5% 1/10W 0603")
      (fields (field (name "PART") "311-32.4KDCT-ND") (field (name "Comment") "Resistor 0603"))
      (libsource (lib "Library_Microgrid") (part "Resistor 0603"))
    )
    (comp (ref "R17")
      (value "3.9k")
      (footprint "0603 (1608 Metric)")
      (description "RES SMD 3.9K OHM 5% 1/10W 0603")
      (fields (field (name "PART") "541-3.9KGCT-ND") (field (name "Comment") "Resistor 0603"))
      (libsource (lib "Library_Microgrid") (part "Resistor 0603"))
    )
    (comp (ref "R18")
      (value "10k")
      (footprint "0603 (1608 Metric)")
      (description "RES SMD 10K OHM 0.5% 1/16W 0603")
      (fields (field (name "PART") "RR08P10.0KDCT-ND") (field (name "Comment") "Resistor 0603"))
      (libsource (lib "Library_Microgrid") (part "Resistor 0603"))
    )
    (comp (ref "R19")
      (value "NC")
      (footprint "0603 (1608 Metric)")
      (description "Resistor 0603")
      (fields (field (name "ALTIUM_VALUE") "160k"))
      (libsource (lib "Library_Microgrid") (part "Resistor 0603"))
    )
    (comp (ref "R20")
      (value "12R")
      (footprint "1206")
      (description "12 Ohm ±0.5% 0.25W, 1/4W Chip Resistor 1206")
      (fields (field (name "PART") "311-2961-1-ND") (field (name "Comment") "Resistor 1206"))
      (libsource (lib "Library_Microgrid") (part "Resistor 1206"))
    )
    (comp (ref "R21")
      (value "0R")
      (footprint "0603 (1608 Metric)")
      (description "RES SMD 10 OHM 0.05% 1/10W 0603")
      (fields (field (name "PART") "RNCF0603AKT10R0CT-ND") (field (name "Comment") "Resistor 0603"))
      (libsource (lib "Library_Microgrid") (part "Resistor 0603"))
    )
    (comp (ref "R22")
      (value "0R")
      (footprint "0603 (1608 Metric)")
      (description "RES SMD 10 OHM 0.05% 1/10W 0603")
      (fields (field (name "PART") "RNCF0603AKT10R0CT-ND") (field (name "Comment") "Resistor 0603"))
      (libsource (lib "Library_Microgrid") (part "Resistor 0603"))
    )
    (comp (ref "R23")
      (value "12R")
      (footprint "1206")
      (description "12 Ohm ±0.5% 0.25W, 1/4W Chip Resistor 1206")
      (fields (field (name "PART") "311-2961-1-ND") (field (name "Comment") "Resistor 1206"))
      (libsource (lib "Library_Microgrid") (part "Resistor 1206"))
    )
    (comp (ref "R24")
      (value "3.9k")
      (footprint "0603 (1608 Metric)")
      (description "RES SMD 3.9K OHM 5% 1/10W 0603")
      (fields (field (name "PART") "541-3.9KGCT-ND") (field (name "Comment") "Resistor 0603"))
      (libsource (lib "Library_Microgrid") (part "Resistor 0603"))
    )
    (comp (ref "R25")
      (value "32.4k")
      (footprint "0603 (1608 Metric)")
      (description "RES SMD 32.4KOHM 0.5% 1/10W 0603")
      (fields (field (name "PART") "311-32.4KDCT-ND") (field (name "Comment") "Resistor 0603"))
      (libsource (lib "Library_Microgrid") (part "Resistor 0603"))
    )
    (comp (ref "R26")
      (value "3.9k")
      (footprint "0603 (1608 Metric)")
      (description "RES SMD 3.9K OHM 5% 1/10W 0603")
      (fields (field (name "PART") "541-3.9KGCT-ND") (field (name "Comment") "Resistor 0603"))
      (libsource (lib "Library_Microgrid") (part "Resistor 0603"))
    )
    (comp (ref "R27")
      (value "10k")
      (footprint "0603 (1608 Metric)")
      (description "RES SMD 10K OHM 0.5% 1/16W 0603")
      (fields (field (name "PART") "RR08P10.0KDCT-ND") (field (name "Comment") "Resistor 0603"))
      (libsource (lib "Library_Microgrid") (part "Resistor 0603"))
    )
    (comp (ref "R28")
      (value "NC")
      (footprint "0603 (1608 Metric)")
      (description "Resistor 0603")
      (fields (field (name "ALTIUM_VALUE") "160k"))
      (libsource (lib "Library_Microgrid") (part "Resistor 0603"))
    )
    (comp (ref "R29")
      (value "12R")
      (footprint "1206")
      (description "12 Ohm ±0.5% 0.25W, 1/4W Chip Resistor 1206")
      (fields (field (name "PART") "311-2961-1-ND") (field (name "Comment") "Resistor 1206"))
      (libsource (lib "Library_Microgrid") (part "Resistor 1206"))
    )
    (comp (ref "R30")
      (value "10R")
      (footprint "0603 (1608 Metric)")
      (description "RES SMD 10 OHM 0.05% 1/10W 0603")
      (fields (field (name "PART") "RNCF0603AKT10R0CT-ND") (field (name "Comment") "Resistor 0603"))
      (libsource (lib "Library_Microgrid") (part "Resistor 0603"))
    )
    (comp (ref "R31")
      (value "10R")
      (footprint "0603 (1608 Metric)")
      (description "RES SMD 10 OHM 0.05% 1/10W 0603")
      (fields (field (name "PART") "RNCF0603AKT10R0CT-ND") (field (name "Comment") "Resistor 0603"))
      (libsource (lib "Library_Microgrid") (part "Resistor 0603"))
    )
    (comp (ref "R32")
      (value "12R")
      (footprint "1206")
      (description "12 Ohm ±0.5% 0.25W, 1/4W Chip Resistor 1206")
      (fields (field (name "PART") "311-2961-1-ND") (field (name "Comment") "Resistor 1206"))
      (libsource (lib "Library_Microgrid") (part "Resistor 1206"))
    )
    (comp (ref "R33")
      (value "3.9k")
      (footprint "0603 (1608 Metric)")
      (description "RES SMD 3.9K OHM 5% 1/10W 0603")
      (fields (field (name "PART") "541-3.9KGCT-ND") (field (name "Comment") "Resistor 0603"))
      (libsource (lib "Library_Microgrid") (part "Resistor 0603"))
    )
    (comp (ref "R34")
      (value "32.4k")
      (footprint "0603 (1608 Metric)")
      (description "RES SMD 32.4KOHM 0.5% 1/10W 0603")
      (fields (field (name "PART") "311-32.4KDCT-ND") (field (name "Comment") "Resistor 0603"))
      (libsource (lib "Library_Microgrid") (part "Resistor 0603"))
    )
    (comp (ref "R35")
      (value "3.9k")
      (footprint "0603 (1608 Metric)")
      (description "RES SMD 3.9K OHM 5% 1/10W 0603")
      (fields (field (name "PART") "541-3.9KGCT-ND") (field (name "Comment") "Resistor 0603"))
      (libsource (lib "Library_Microgrid") (part "Resistor 0603"))
    )
    (comp (ref "R36")
      (value "10k")
      (footprint "0603 (1608 Metric)")
      (description "RES SMD 10K OHM 0.5% 1/16W 0603")
      (fields (field (name "PART") "RR08P10.0KDCT-ND") (field (name "Comment") "Resistor 0603"))
      (libsource (lib "Library_Microgrid") (part "Resistor 0603"))
    )
    (comp (ref "T1")
      (value "750313769")
      (footprint "Xmr SN6501")
      (description "TRANSFORMER SMD TR1.7 SN6501")
      (fields (field (name "PART") "1297-1107-1-ND"))
      (libsource (lib "Library_Microgrid") (part "750313769"))
    )
    (comp (ref "T2")
      (value "750313769")
      (footprint "Xmr SN6501")
      (description "TRANSFORMER SMD TR1.7 SN6501")
      (fields (field (name "PART") "1297-1107-1-ND"))
      (libsource (lib "Library_Microgrid") (part "750313769"))
    )
    (comp (ref "T3")
      (value "750313769")
      (footprint "Xmr SN6501")
      (description "TRANSFORMER SMD TR1.7 SN6501")
      (fields (field (name "PART") "1297-1107-1-ND"))
      (libsource (lib "Library_Microgrid") (part "750313769"))
    )
    (comp (ref "U1")
      (value "AMC1100")
      (footprint "SOIC8")
      (description "IC OPAMP ISOLATION 100KHZ 8SOIC")
      (fields (field (name "PART") "296-38822-5-ND"))
      (libsource (lib "Library_Microgrid") (part "AMC1100"))
    )
    (comp (ref "U2")
      (value "TLV70450DBV")
      (footprint "SOT23-5")
      (description "IC REG LDO 5V 0.15A SOT23-5")
      (fields (field (name "PART") "296-39287-1-ND"))
      (libsource (lib "Library_Microgrid") (part "TLV70450DBV"))
    )
    (comp (ref "U3")
      (value "SN6501")
      (footprint "SOT23-5")
      (description "IC REG CONV PWR SUPPLIES SOT23-5")
      (fields (field (name "PART") "296-37700-1-ND"))
      (libsource (lib "Library_Microgrid") (part "SN6501"))
    )
    (comp (ref "U4")
      (value "TPS7A30")
      (footprint "8-TSSOP")
      (description "IC REG LDO NEG ADJ 0.2A 8MSOP")
      (fields (field (name "PART") "296-27750-1-ND"))
      (libsource (lib "Library_Microgrid") (part "TPS7A30"))
    )
    (comp (ref "U5")
      (value "AMC1100")
      (footprint "SOIC8")
      (description "IC OPAMP ISOLATION 100KHZ 8SOIC")
      (fields (field (name "PART") "296-38822-5-ND"))
      (libsource (lib "Library_Microgrid") (part "AMC1100"))
    )
    (comp (ref "U6")
      (value "TLV70450DBV")
      (footprint "SOT23-5")
      (description "IC REG LDO 5V 0.15A SOT23-5")
      (fields (field (name "PART") "296-39287-1-ND"))
      (libsource (lib "Library_Microgrid") (part "TLV70450DBV"))
    )
    (comp (ref "U7")
      (value "SN6501")
      (footprint "SOT23-5")
      (description "IC REG CONV PWR SUPPLIES SOT23-5")
      (fields (field (name "PART") "296-37700-1-ND"))
      (libsource (lib "Library_Microgrid") (part "SN6501"))
    )
    (comp (ref "U8")
      (value "TPS7A30")
      (footprint "8-TSSOP")
      (description "IC REG LDO NEG ADJ 0.2A 8MSOP")
      (fields (field (name "PART") "296-27750-1-ND"))
      (libsource (lib "Library_Microgrid") (part "TPS7A30"))
    )
    (comp (ref "U9")
      (value "AMC1100")
      (footprint "SOIC8")
      (description "IC OPAMP ISOLATION 100KHZ 8SOIC")
      (fields (field (name "PART") "296-38822-5-ND"))
      (libsource (lib "Library_Microgrid") (part "AMC1100"))
    )
    (comp (ref "U10")
      (value "TLV70450DBV")
      (footprint "SOT23-5")
      (description "IC REG LDO 5V 0.15A SOT23-5")
      (fields (field (name "PART") "296-39287-1-ND"))
      (libsource (lib "Library_Microgrid") (part "TLV70450DBV"))
    )
    (comp (ref "U11")
      (value "SN6501")
      (footprint "SOT23-5")
      (description "IC REG CONV PWR SUPPLIES SOT23-5")
      (fields (field (name "PART") "296-37700-1-ND"))
      (libsource (lib "Library_Microgrid") (part "SN6501"))
    )
    (comp (ref "U12")
      (value "TPS7A30")
      (footprint "8-TSSOP")
      (description "IC REG LDO NEG ADJ 0.2A 8MSOP")
      (fields (field (name "PART") "296-27750-1-ND"))
      (libsource (lib "Library_Microgrid") (part "TPS7A30"))
    )
  )
  (nets
    (net (code "1") (name "+5V_IA1") (class "Default")
      (node (ref "C60") (pin "2") (pinfunction "OUT_2") (pintype "passive"))
      (node (ref "C62") (pin "2") (pinfunction "OUT_2") (pintype "passive"))
      (node (ref "C72") (pin "2") (pinfunction "OUT_2") (pintype "passive"))
      (node (ref "C73") (pin "2") (pinfunction "OUT_2") (pintype "passive"))
      (node (ref "D17") (pin "2") (pinfunction "node_2") (pintype "passive"))
      (node (ref "D18") (pin "2") (pinfunction "node_2") (pintype "passive"))
      (node (ref "D20") (pin "A") (pinfunction "A_A") (pintype "passive"))
      (node (ref "D21") (pin "1") (pinfunction "Anode_1") (pintype "passive"))
      (node (ref "FB11") (pin "2") (pinfunction "OUT_2") (pintype "passive"))
      (node (ref "R28") (pin "2") (pinfunction "A_2") (pintype "passive"))
      (node (ref "U9") (pin "1") (pinfunction "V+_1") (pintype "passive"))
    )
    (net (code "2") (name "+5V_IB1") (class "Default")
      (node (ref "C10") (pin "2") (pinfunction "OUT_2") (pintype "passive"))
      (node (ref "C12") (pin "2") (pinfunction "OUT_2") (pintype "passive"))
      (node (ref "C22") (pin "2") (pinfunction "OUT_2") (pintype "passive"))
      (node (ref "C23") (pin "2") (pinfunction "OUT_2") (pintype "passive"))
      (node (ref "D1") (pin "2") (pinfunction "node_2") (pintype "passive"))
      (node (ref "D2") (pin "2") (pinfunction "node_2") (pintype "passive"))
      (node (ref "D4") (pin "A") (pinfunction "A_A") (pintype "passive"))
      (node (ref "D5") (pin "1") (pinfunction "Anode_1") (pintype "passive"))
      (node (ref "FB3") (pin "2") (pinfunction "OUT_2") (pintype "passive"))
      (node (ref "R10") (pin "2") (pinfunction "A_2") (pintype "passive"))
      (node (ref "U1") (pin "1") (pinfunction "V+_1") (pintype "passive"))
    )
    (net (code "3") (name "+5V_IC1") (class "Default")
      (node (ref "C35") (pin "2") (pinfunction "OUT_2") (pintype "passive"))
      (node (ref "C37") (pin "2") (pinfunction "OUT_2") (pintype "passive"))
      (node (ref "C47") (pin "2") (pinfunction "OUT_2") (pintype "passive"))
      (node (ref "C48") (pin "2") (pinfunction "OUT_2") (pintype "passive"))
      (node (ref "D10") (pin "2") (pinfunction "node_2") (pintype "passive"))
      (node (ref "D12") (pin "A") (pinfunction "A_A") (pintype "passive"))
      (node (ref "D13") (pin "1") (pinfunction "Anode_1") (pintype "passive"))
      (node (ref "D9") (pin "2") (pinfunction "node_2") (pintype "passive"))
      (node (ref "FB7") (pin "2") (pinfunction "OUT_2") (pintype "passive"))
      (node (ref "R19") (pin "2") (pinfunction "A_2") (pintype "passive"))
      (node (ref "U5") (pin "1") (pinfunction "V+_1") (pintype "passive"))
    )
    (net (code "4") (name "+5V_LV") (class "Default")
      (node (ref "C11") (pin "1") (pinfunction "OUT_1") (pintype "passive"))
      (node (ref "C13") (pin "1") (pinfunction "OUT_1") (pintype "passive"))
      (node (ref "C16") (pin "2") (pinfunction "OUT_2") (pintype "passive"))
      (node (ref "C17") (pin "2") (pinfunction "OUT_2") (pintype "passive"))
      (node (ref "C18") (pin "2") (pinfunction "OUT_2") (pintype "passive"))
      (node (ref "C36") (pin "1") (pinfunction "OUT_1") (pintype "passive"))
      (node (ref "C38") (pin "1") (pinfunction "OUT_1") (pintype "passive"))
      (node (ref "C41") (pin "2") (pinfunction "OUT_2") (pintype "passive"))
      (node (ref "C42") (pin "2") (pinfunction "OUT_2") (pintype "passive"))
      (node (ref "C43") (pin "2") (pinfunction "OUT_2") (pintype "passive"))
      (node (ref "C61") (pin "1") (pinfunction "OUT_1") (pintype "passive"))
      (node (ref "C63") (pin "1") (pinfunction "OUT_1") (pintype "passive"))
      (node (ref "C66") (pin "2") (pinfunction "OUT_2") (pintype "passive"))
      (node (ref "C67") (pin "2") (pinfunction "OUT_2") (pintype "passive"))
      (node (ref "C68") (pin "2") (pinfunction "OUT_2") (pintype "passive"))
      (node (ref "T1") (pin "2") (pinfunction "1_2") (pintype "passive"))
      (node (ref "T2") (pin "2") (pinfunction "1_2") (pintype "passive"))
      (node (ref "T3") (pin "2") (pinfunction "1_2") (pintype "passive"))
      (node (ref "U1") (pin "8") (pinfunction "V+_8") (pintype "passive"))
      (node (ref "U11") (pin "2") (pinfunction "VCC_2") (pintype "passive"))
      (node (ref "U3") (pin "2") (pinfunction "VCC_2") (pintype "passive"))
      (node (ref "U5") (pin "8") (pinfunction "V+_8") (pintype "passive"))
      (node (ref "U7") (pin "2") (pinfunction "VCC_2") (pintype "passive"))
      (node (ref "U9") (pin "8") (pinfunction "V+_8") (pintype "passive"))
    )
    (net (code "5") (name "+6V_IA1") (class "Default")
      (node (ref "C69") (pin "2") (pinfunction "OUT_2") (pintype "passive"))
      (node (ref "C70") (pin "2") (pinfunction "OUT_2") (pintype "passive"))
      (node (ref "C76") (pin "2") (pinfunction "OUT_2") (pintype "passive"))
      (node (ref "C77") (pin "2") (pinfunction "OUT_2") (pintype "passive"))
      (node (ref "D19") (pin "2") (pinfunction "Anode_2") (pintype "passive"))
      (node (ref "U10") (pin "2") (pinfunction "IN_2") (pintype "passive"))
    )
    (net (code "6") (name "+6V_IB1") (class "Default")
      (node (ref "C19") (pin "2") (pinfunction "OUT_2") (pintype "passive"))
      (node (ref "C20") (pin "2") (pinfunction "OUT_2") (pintype "passive"))
      (node (ref "C26") (pin "2") (pinfunction "OUT_2") (pintype "passive"))
      (node (ref "C27") (pin "2") (pinfunction "OUT_2") (pintype "passive"))
      (node (ref "D3") (pin "2") (pinfunction "Anode_2") (pintype "passive"))
      (node (ref "U2") (pin "2") (pinfunction "IN_2") (pintype "passive"))
    )
    (net (code "7") (name "+6V_IC1") (class "Default")
      (node (ref "C44") (pin "2") (pinfunction "OUT_2") (pintype "passive"))
      (node (ref "C45") (pin "2") (pinfunction "OUT_2") (pintype "passive"))
      (node (ref "C51") (pin "2") (pinfunction "OUT_2") (pintype "passive"))
      (node (ref "C52") (pin "2") (pinfunction "OUT_2") (pintype "passive"))
      (node (ref "D11") (pin "2") (pinfunction "Anode_2") (pintype "passive"))
      (node (ref "U6") (pin "2") (pinfunction "IN_2") (pintype "passive"))
    )
    (net (code "8") (name "-5V_IA1") (class "Default")
      (node (ref "C81") (pin "2") (pinfunction "OUT_2") (pintype "passive"))
      (node (ref "C82") (pin "2") (pinfunction "OUT_2") (pintype "passive"))
      (node (ref "D17") (pin "1") (pinfunction "node_1") (pintype "passive"))
      (node (ref "D18") (pin "1") (pinfunction "node_1") (pintype "passive"))
      (node (ref "D23") (pin "K") (pinfunction "K_K") (pintype "passive"))
      (node (ref "D24") (pin "2") (pinfunction "Anode_2") (pintype "passive"))
      (node (ref "FB12") (pin "2") (pinfunction "OUT_2") (pintype "passive"))
    )
    (net (code "9") (name "-5V_IB1") (class "Default")
      (node (ref "C31") (pin "2") (pinfunction "OUT_2") (pintype "passive"))
      (node (ref "C32") (pin "2") (pinfunction "OUT_2") (pintype "passive"))
      (node (ref "D1") (pin "1") (pinfunction "node_1") (pintype "passive"))
      (node (ref "D2") (pin "1") (pinfunction "node_1") (pintype "passive"))
      (node (ref "D7") (pin "K") (pinfunction "K_K") (pintype "passive"))
      (node (ref "D8") (pin "2") (pinfunction "Anode_2") (pintype "passive"))
      (node (ref "FB4") (pin "2") (pinfunction "OUT_2") (pintype "passive"))
    )
    (net (code "10") (name "-5V_IC1") (class "Default")
      (node (ref "C56") (pin "2") (pinfunction "OUT_2") (pintype "passive"))
      (node (ref "C57") (pin "2") (pinfunction "OUT_2") (pintype "passive"))
      (node (ref "D10") (pin "1") (pinfunction "node_1") (pintype "passive"))
      (node (ref "D15") (pin "K") (pinfunction "K_K") (pintype "passive"))
      (node (ref "D16") (pin "2") (pinfunction "Anode_2") (pintype "passive"))
      (node (ref "D9") (pin "1") (pinfunction "node_1") (pintype "passive"))
      (node (ref "FB8") (pin "2") (pinfunction "OUT_2") (pintype "passive"))
    )
    (net (code "11") (name "-6V_IA1") (class "Default")
      (node (ref "C74") (pin "1") (pinfunction "OUT_1") (pintype "passive"))
      (node (ref "C75") (pin "1") (pinfunction "OUT_1") (pintype "passive"))
      (node (ref "C78") (pin "2") (pinfunction "OUT_2") (pintype "passive"))
      (node (ref "C79") (pin "2") (pinfunction "OUT_2") (pintype "passive"))
      (node (ref "D22") (pin "1") (pinfunction "Anode_1") (pintype "passive"))
      (node (ref "U12") (pin "5") (pinfunction "EN_5") (pintype "passive"))
      (node (ref "U12") (pin "8") (pinfunction "VIN_8") (pintype "power_in"))
    )
    (net (code "12") (name "-6V_IB1") (class "Default")
      (node (ref "C24") (pin "1") (pinfunction "OUT_1") (pintype "passive"))
      (node (ref "C25") (pin "1") (pinfunction "OUT_1") (pintype "passive"))
      (node (ref "C28") (pin "2") (pinfunction "OUT_2") (pintype "passive"))
      (node (ref "C29") (pin "2") (pinfunction "OUT_2") (pintype "passive"))
      (node (ref "D6") (pin "1") (pinfunction "Anode_1") (pintype "passive"))
      (node (ref "U4") (pin "5") (pinfunction "EN_5") (pintype "passive"))
      (node (ref "U4") (pin "8") (pinfunction "VIN_8") (pintype "power_in"))
    )
    (net (code "13") (name "-6V_IC1") (class "Default")
      (node (ref "C49") (pin "1") (pinfunction "OUT_1") (pintype "passive"))
      (node (ref "C50") (pin "1") (pinfunction "OUT_1") (pintype "passive"))
      (node (ref "C53") (pin "2") (pinfunction "OUT_2") (pintype "passive"))
      (node (ref "C54") (pin "2") (pinfunction "OUT_2") (pintype "passive"))
      (node (ref "D14") (pin "1") (pinfunction "Anode_1") (pintype "passive"))
      (node (ref "U8") (pin "5") (pinfunction "EN_5") (pintype "passive"))
      (node (ref "U8") (pin "8") (pinfunction "VIN_8") (pintype "power_in"))
    )
    (net (code "14") (name "/IA1") (class "Default")
      (node (ref "FB9") (pin "1") (pinfunction "OUT_1") (pintype "passive"))
    )
    (net (code "15") (name "/IB1") (class "Default")
      (node (ref "FB1") (pin "1") (pinfunction "OUT_1") (pintype "passive"))
    )
    (net (code "16") (name "/IC1") (class "Default")
      (node (ref "FB5") (pin "1") (pinfunction "OUT_1") (pintype "passive"))
    )
    (net (code "17") (name "/OUT_IA1N") (class "Default")
      (node (ref "R31") (pin "2") (pinfunction "A_2") (pintype "passive"))
    )
    (net (code "18") (name "/OUT_IA1P") (class "Default")
      (node (ref "R30") (pin "2") (pinfunction "A_2") (pintype "passive"))
    )
    (net (code "19") (name "/OUT_IB1N") (class "Default")
      (node (ref "R13") (pin "2") (pinfunction "A_2") (pintype "passive"))
    )
    (net (code "20") (name "/OUT_IB1P") (class "Default")
      (node (ref "R12") (pin "2") (pinfunction "A_2") (pintype "passive"))
    )
    (net (code "21") (name "/OUT_IC1N") (class "Default")
      (node (ref "R22") (pin "2") (pinfunction "A_2") (pintype "passive"))
    )
    (net (code "22") (name "/OUT_IC1P") (class "Default")
      (node (ref "R21") (pin "2") (pinfunction "A_2") (pintype "passive"))
    )
    (net (code "23") (name "GND_IA1") (class "Default")
      (node (ref "C60") (pin "1") (pinfunction "OUT_1") (pintype "passive"))
      (node (ref "C62") (pin "1") (pinfunction "OUT_1") (pintype "passive"))
      (node (ref "C65") (pin "2") (pinfunction "2_2") (pintype "passive"))
      (node (ref "C69") (pin "1") (pinfunction "OUT_1") (pintype "passive"))
      (node (ref "C70") (pin "1") (pinfunction "OUT_1") (pintype "passive"))
      (node (ref "C71") (pin "1") (pinfunction "OUT_1") (pintype "passive"))
      (node (ref "C72") (pin "1") (pinfunction "OUT_1") (pintype "passive"))
      (node (ref "C73") (pin "1") (pinfunction "OUT_1") (pintype "passive"))
      (node (ref "C74") (pin "2") (pinfunction "OUT_2") (pintype "passive"))
      (node (ref "C75") (pin "2") (pinfunction "OUT_2") (pintype "passive"))
      (node (ref "C76") (pin "1") (pinfunction "OUT_1") (pintype "passive"))
      (node (ref "C77") (pin "1") (pinfunction "OUT_1") (pintype "passive"))
      (node (ref "C78") (pin "1") (pinfunction "OUT_1") (pintype "passive"))
      (node (ref "C79") (pin "1") (pinfunction "OUT_1") (pintype "passive"))
      (node (ref "C81") (pin "1") (pinfunction "OUT_1") (pintype "passive"))
      (node (ref "C82") (pin "1") (pinfunction "OUT_1") (pintype "passive"))
      (node (ref "C83") (pin "1") (pinfunction "OUT_1") (pintype "passive"))
      (node (ref "C84") (pin "1") (pinfunction "OUT_1") (pintype "passive"))
      (node (ref "D21") (pin "2") (pinfunction "Anode_2") (pintype "passive"))
      (node (ref "D24") (pin "1") (pinfunction "Anode_1") (pintype "passive"))
      (node (ref "FB10") (pin "1") (pinfunction "OUT_1") (pintype "passive"))
      (node (ref "R33") (pin "1") (pinfunction "A_1") (pintype "passive"))
      (node (ref "R35") (pin "1") (pinfunction "A_1") (pintype "passive"))
      (node (ref "R36") (pin "1") (pinfunction "A_1") (pintype "passive"))
      (node (ref "T3") (pin "4") (pinfunction "1_4") (pintype "passive"))
      (node (ref "U10") (pin "1") (pinfunction "GND_1") (pintype "passive"))
      (node (ref "U12") (pin "3") (pinfunction "NC_3") (pintype "passive"))
      (node (ref "U12") (pin "4") (pinfunction "GND_4") (pintype "power_in"))
      (node (ref "U12") (pin "9") (pinfunction "TPAD_9") (pintype "power_in"))
      (node (ref "U9") (pin "4") (pinfunction "V-_4") (pintype "passive"))
    )
    (net (code "24") (name "GND_IB1") (class "Default")
      (node (ref "C10") (pin "1") (pinfunction "OUT_1") (pintype "passive"))
      (node (ref "C12") (pin "1") (pinfunction "OUT_1") (pintype "passive"))
      (node (ref "C15") (pin "2") (pinfunction "2_2") (pintype "passive"))
      (node (ref "C19") (pin "1") (pinfunction "OUT_1") (pintype "passive"))
      (node (ref "C20") (pin "1") (pinfunction "OUT_1") (pintype "passive"))
      (node (ref "C21") (pin "1") (pinfunction "OUT_1") (pintype "passive"))
      (node (ref "C22") (pin "1") (pinfunction "OUT_1") (pintype "passive"))
      (node (ref "C23") (pin "1") (pinfunction "OUT_1") (pintype "passive"))
      (node (ref "C24") (pin "2") (pinfunction "OUT_2") (pintype "passive"))
      (node (ref "C25") (pin "2") (pinfunction "OUT_2") (pintype "passive"))
      (node (ref "C26") (pin "1") (pinfunction "OUT_1") (pintype "passive"))
      (node (ref "C27") (pin "1") (pinfunction "OUT_1") (pintype "passive"))
      (node (ref "C28") (pin "1") (pinfunction "OUT_1") (pintype "passive"))
      (node (ref "C29") (pin "1") (pinfunction "OUT_1") (pintype "passive"))
      (node (ref "C31") (pin "1") (pinfunction "OUT_1") (pintype "passive"))
      (node (ref "C32") (pin "1") (pinfunction "OUT_1") (pintype "passive"))
      (node (ref "C33") (pin "1") (pinfunction "OUT_1") (pintype "passive"))
      (node (ref "C34") (pin "1") (pinfunction "OUT_1") (pintype "passive"))
      (node (ref "D5") (pin "2") (pinfunction "Anode_2") (pintype "passive"))
      (node (ref "D8") (pin "1") (pinfunction "Anode_1") (pintype "passive"))
      (node (ref "FB2") (pin "1") (pinfunction "OUT_1") (pintype "passive"))
      (node (ref "R15") (pin "1") (pinfunction "A_1") (pintype "passive"))
      (node (ref "R17") (pin "1") (pinfunction "A_1") (pintype "passive"))
      (node (ref "R27") (pin "1") (pinfunction "A_1") (pintype "passive"))
      (node (ref "T1") (pin "4") (pinfunction "1_4") (pintype "passive"))
      (node (ref "U1") (pin "4") (pinfunction "V-_4") (pintype "passive"))
      (node (ref "U2") (pin "1") (pinfunction "GND_1") (pintype "passive"))
      (node (ref "U4") (pin "3") (pinfunction "NC_3") (pintype "passive"))
      (node (ref "U4") (pin "4") (pinfunction "GND_4") (pintype "power_in"))
      (node (ref "U4") (pin "9") (pinfunction "TPAD_9") (pintype "power_in"))
    )
    (net (code "25") (name "GND_IC1") (class "Default")
      (node (ref "C35") (pin "1") (pinfunction "OUT_1") (pintype "passive"))
      (node (ref "C37") (pin "1") (pinfunction "OUT_1") (pintype "passive"))
      (node (ref "C40") (pin "2") (pinfunction "2_2") (pintype "passive"))
      (node (ref "C44") (pin "1") (pinfunction "OUT_1") (pintype "passive"))
      (node (ref "C45") (pin "1") (pinfunction "OUT_1") (pintype "passive"))
      (node (ref "C46") (pin "1") (pinfunction "OUT_1") (pintype "passive"))
      (node (ref "C47") (pin "1") (pinfunction "OUT_1") (pintype "passive"))
      (node (ref "C48") (pin "1") (pinfunction "OUT_1") (pintype "passive"))
      (node (ref "C49") (pin "2") (pinfunction "OUT_2") (pintype "passive"))
      (node (ref "C50") (pin "2") (pinfunction "OUT_2") (pintype "passive"))
      (node (ref "C51") (pin "1") (pinfunction "OUT_1") (pintype "passive"))
      (node (ref "C52") (pin "1") (pinfunction "OUT_1") (pintype "passive"))
      (node (ref "C53") (pin "1") (pinfunction "OUT_1") (pintype "passive"))
      (node (ref "C54") (pin "1") (pinfunction "OUT_1") (pintype "passive"))
      (node (ref "C56") (pin "1") (pinfunction "OUT_1") (pintype "passive"))
      (node (ref "C57") (pin "1") (pinfunction "OUT_1") (pintype "passive"))
      (node (ref "C58") (pin "1") (pinfunction "OUT_1") (pintype "passive"))
      (node (ref "C59") (pin "1") (pinfunction "OUT_1") (pintype "passive"))
      (node (ref "D13") (pin "2") (pinfunction "Anode_2") (pintype "passive"))
      (node (ref "D16") (pin "1") (pinfunction "Anode_1") (pintype "passive"))
      (node (ref "FB6") (pin "1") (pinfunction "OUT_1") (pintype "passive"))
      (node (ref "R18") (pin "1") (pinfunction "A_1") (pintype "passive"))
      (node (ref "R24") (pin "1") (pinfunction "A_1") (pintype "passive"))
      (node (ref "R26") (pin "1") (pinfunction "A_1") (pintype "passive"))
      (node (ref "T2") (pin "4") (pinfunction "1_4") (pintype "passive"))
      (node (ref "U5") (pin "4") (pinfunction "V-_4") (pintype "passive"))
      (node (ref "U6") (pin "1") (pinfunction "GND_1") (pintype "passive"))
      (node (ref "U8") (pin "3") (pinfunction "NC_3") (pintype "passive"))
      (node (ref "U8") (pin "4") (pinfunction "GND_4") (pintype "power_in"))
      (node (ref "U8") (pin "9") (pinfunction "TPAD_9") (pintype "power_in"))
    )
    (net (code "26") (name "GND_LV") (class "Default")
      (node (ref "C11") (pin "2") (pinfunction "OUT_2") (pintype "passive"))
      (node (ref "C13") (pin "2") (pinfunction "OUT_2") (pintype "passive"))
      (node (ref "C15") (pin "1") (pinfunction "1_1") (pintype "passive"))
      (node (ref "C16") (pin "1") (pinfunction "OUT_1") (pintype "passive"))
      (node (ref "C17") (pin "1") (pinfunction "OUT_1") (pintype "passive"))
      (node (ref "C18") (pin "1") (pinfunction "OUT_1") (pintype "passive"))
      (node (ref "C36") (pin "2") (pinfunction "OUT_2") (pintype "passive"))
      (node (ref "C38") (pin "2") (pinfunction "OUT_2") (pintype "passive"))
      (node (ref "C40") (pin "1") (pinfunction "1_1") (pintype "passive"))
      (node (ref "C41") (pin "1") (pinfunction "OUT_1") (pintype "passive"))
      (node (ref "C42") (pin "1") (pinfunction "OUT_1") (pintype "passive"))
      (node (ref "C43") (pin "1") (pinfunction "OUT_1") (pintype "passive"))
      (node (ref "C61") (pin "2") (pinfunction "OUT_2") (pintype "passive"))
      (node (ref "C63") (pin "2") (pinfunction "OUT_2") (pintype "passive"))
      (node (ref "C65") (pin "1") (pinfunction "1_1") (pintype "passive"))
      (node (ref "C66") (pin "1") (pinfunction "OUT_1") (pintype "passive"))
      (node (ref "C67") (pin "1") (pinfunction "OUT_1") (pintype "passive"))
      (node (ref "C68") (pin "1") (pinfunction "OUT_1") (pintype "passive"))
      (node (ref "U1") (pin "5") (pinfunction "V-_5") (pintype "passive"))
      (node (ref "U11") (pin "4") (pinfunction "GND_4") (pintype "passive"))
      (node (ref "U11") (pin "5") (pinfunction "GND_5") (pintype "passive"))
      (node (ref "U3") (pin "4") (pinfunction "GND_4") (pintype "passive"))
      (node (ref "U3") (pin "5") (pinfunction "GND_5") (pintype "passive"))
      (node (ref "U5") (pin "5") (pinfunction "V-_5") (pintype "passive"))
      (node (ref "U7") (pin "4") (pinfunction "GND_4") (pintype "passive"))
      (node (ref "U7") (pin "5") (pinfunction "GND_5") (pintype "passive"))
      (node (ref "U9") (pin "5") (pinfunction "V-_5") (pintype "passive"))
    )
    (net (code "27") (name "Net-(C14-OUT-Pad1)") (class "Default")
      (node (ref "C14") (pin "1") (pinfunction "OUT_1") (pintype "passive"))
      (node (ref "D1") (pin "3") (pinfunction "node_3") (pintype "passive"))
      (node (ref "R10") (pin "1") (pinfunction "A_1") (pintype "passive"))
      (node (ref "R11") (pin "2") (pinfunction "A_2") (pintype "passive"))
      (node (ref "U1") (pin "2") (pinfunction "+_2") (pintype "passive"))
    )
    (net (code "28") (name "Net-(C14-OUT-Pad2)") (class "Default")
      (node (ref "C14") (pin "2") (pinfunction "OUT_2") (pintype "passive"))
      (node (ref "D2") (pin "3") (pinfunction "node_3") (pintype "passive"))
      (node (ref "R14") (pin "2") (pinfunction "A_2") (pintype "passive"))
      (node (ref "U1") (pin "3") (pinfunction "-_3") (pintype "passive"))
    )
    (net (code "29") (name "Net-(C39-OUT-Pad1)") (class "Default")
      (node (ref "C39") (pin "1") (pinfunction "OUT_1") (pintype "passive"))
      (node (ref "D9") (pin "3") (pinfunction "node_3") (pintype "passive"))
      (node (ref "R19") (pin "1") (pinfunction "A_1") (pintype "passive"))
      (node (ref "R20") (pin "2") (pinfunction "A_2") (pintype "passive"))
      (node (ref "U5") (pin "2") (pinfunction "+_2") (pintype "passive"))
    )
    (net (code "30") (name "Net-(C39-OUT-Pad2)") (class "Default")
      (node (ref "C39") (pin "2") (pinfunction "OUT_2") (pintype "passive"))
      (node (ref "D10") (pin "3") (pinfunction "node_3") (pintype "passive"))
      (node (ref "R23") (pin "2") (pinfunction "A_2") (pintype "passive"))
      (node (ref "U5") (pin "3") (pinfunction "-_3") (pintype "passive"))
    )
    (net (code "31") (name "Net-(C64-OUT-Pad1)") (class "Default")
      (node (ref "C64") (pin "1") (pinfunction "OUT_1") (pintype "passive"))
      (node (ref "D17") (pin "3") (pinfunction "node_3") (pintype "passive"))
      (node (ref "R28") (pin "1") (pinfunction "A_1") (pintype "passive"))
      (node (ref "R29") (pin "2") (pinfunction "A_2") (pintype "passive"))
      (node (ref "U9") (pin "2") (pinfunction "+_2") (pintype "passive"))
    )
    (net (code "32") (name "Net-(C64-OUT-Pad2)") (class "Default")
      (node (ref "C64") (pin "2") (pinfunction "OUT_2") (pintype "passive"))
      (node (ref "D18") (pin "3") (pinfunction "node_3") (pintype "passive"))
      (node (ref "R32") (pin "2") (pinfunction "A_2") (pintype "passive"))
      (node (ref "U9") (pin "3") (pinfunction "-_3") (pintype "passive"))
    )
    (net (code "33") (name "Net-(D3-Anode-Pad1)") (class "Default")
      (node (ref "D3") (pin "1") (pinfunction "Anode_1") (pintype "passive"))
      (node (ref "D6") (pin "2") (pinfunction "Anode_2") (pintype "passive"))
      (node (ref "T1") (pin "6") (pinfunction "1_6") (pintype "passive"))
    )
    (net (code "34") (name "Net-(D4-PadK)") (class "Default")
      (node (ref "D4") (pin "K") (pinfunction "K_K") (pintype "passive"))
      (node (ref "R15") (pin "2") (pinfunction "A_2") (pintype "passive"))
    )
    (net (code "35") (name "Net-(D7-PadA)") (class "Default")
      (node (ref "D7") (pin "A") (pinfunction "A_A") (pintype "passive"))
      (node (ref "R17") (pin "2") (pinfunction "A_2") (pintype "passive"))
    )
    (net (code "36") (name "Net-(D11-Anode-Pad1)") (class "Default")
      (node (ref "D11") (pin "1") (pinfunction "Anode_1") (pintype "passive"))
      (node (ref "D14") (pin "2") (pinfunction "Anode_2") (pintype "passive"))
      (node (ref "T2") (pin "6") (pinfunction "1_6") (pintype "passive"))
    )
    (net (code "37") (name "Net-(D12-PadK)") (class "Default")
      (node (ref "D12") (pin "K") (pinfunction "K_K") (pintype "passive"))
      (node (ref "R24") (pin "2") (pinfunction "A_2") (pintype "passive"))
    )
    (net (code "38") (name "Net-(D15-PadA)") (class "Default")
      (node (ref "D15") (pin "A") (pinfunction "A_A") (pintype "passive"))
      (node (ref "R26") (pin "2") (pinfunction "A_2") (pintype "passive"))
    )
    (net (code "39") (name "Net-(D19-Anode-Pad1)") (class "Default")
      (node (ref "D19") (pin "1") (pinfunction "Anode_1") (pintype "passive"))
      (node (ref "D22") (pin "2") (pinfunction "Anode_2") (pintype "passive"))
      (node (ref "T3") (pin "6") (pinfunction "1_6") (pintype "passive"))
    )
    (net (code "40") (name "Net-(D20-PadK)") (class "Default")
      (node (ref "D20") (pin "K") (pinfunction "K_K") (pintype "passive"))
      (node (ref "R33") (pin "2") (pinfunction "A_2") (pintype "passive"))
    )
    (net (code "41") (name "Net-(D23-PadA)") (class "Default")
      (node (ref "D23") (pin "A") (pinfunction "A_A") (pintype "passive"))
      (node (ref "R35") (pin "2") (pinfunction "A_2") (pintype "passive"))
    )
    (net (code "42") (name "Net-(FB1-OUT-Pad2)") (class "Default")
      (node (ref "FB1") (pin "2") (pinfunction "OUT_2") (pintype "passive"))
      (node (ref "R11") (pin "1") (pinfunction "A_1") (pintype "passive"))
    )
    (net (code "43") (name "Net-(FB2-OUT-Pad2)") (class "Default")
      (node (ref "FB2") (pin "2") (pinfunction "OUT_2") (pintype "passive"))
      (node (ref "R14") (pin "1") (pinfunction "A_1") (pintype "passive"))
    )
    (net (code "44") (name "Net-(FB5-OUT-Pad2)") (class "Default")
      (node (ref "FB5") (pin "2") (pinfunction "OUT_2") (pintype "passive"))
      (node (ref "R20") (pin "1") (pinfunction "A_1") (pintype "passive"))
    )
    (net (code "45") (name "Net-(FB6-OUT-Pad2)") (class "Default")
      (node (ref "FB6") (pin "2") (pinfunction "OUT_2") (pintype "passive"))
      (node (ref "R23") (pin "1") (pinfunction "A_1") (pintype "passive"))
    )
    (net (code "46") (name "Net-(FB9-OUT-Pad2)") (class "Default")
      (node (ref "FB9") (pin "2") (pinfunction "OUT_2") (pintype "passive"))
      (node (ref "R29") (pin "1") (pinfunction "A_1") (pintype "passive"))
    )
    (net (code "47") (name "Net-(FB10-OUT-Pad2)") (class "Default")
      (node (ref "FB10") (pin "2") (pinfunction "OUT_2") (pintype "passive"))
      (node (ref "R32") (pin "1") (pinfunction "A_1") (pintype "passive"))
    )
    (net (code "48") (name "Net-(R12-A-Pad1)") (class "Default")
      (node (ref "R12") (pin "1") (pinfunction "A_1") (pintype "passive"))
      (node (ref "U1") (pin "7") (pinfunction "+_7") (pintype "passive"))
    )
    (net (code "49") (name "Net-(R13-A-Pad1)") (class "Default")
      (node (ref "R13") (pin "1") (pinfunction "A_1") (pintype "passive"))
      (node (ref "U1") (pin "6") (pinfunction "-_6") (pintype "passive"))
    )
    (net (code "50") (name "Net-(R21-A-Pad1)") (class "Default")
      (node (ref "R21") (pin "1") (pinfunction "A_1") (pintype "passive"))
      (node (ref "U5") (pin "7") (pinfunction "+_7") (pintype "passive"))
    )
    (net (code "51") (name "Net-(R22-A-Pad1)") (class "Default")
      (node (ref "R22") (pin "1") (pinfunction "A_1") (pintype "passive"))
      (node (ref "U5") (pin "6") (pinfunction "-_6") (pintype "passive"))
    )
    (net (code "52") (name "Net-(R30-A-Pad1)") (class "Default")
      (node (ref "R30") (pin "1") (pinfunction "A_1") (pintype "passive"))
      (node (ref "U9") (pin "7") (pinfunction "+_7") (pintype "passive"))
    )
    (net (code "53") (name "Net-(R31-A-Pad1)") (class "Default")
      (node (ref "R31") (pin "1") (pinfunction "A_1") (pintype "passive"))
      (node (ref "U9") (pin "6") (pinfunction "-_6") (pintype "passive"))
    )
    (net (code "54") (name "Net-(U2-OUT)") (class "Default")
      (node (ref "C21") (pin "2") (pinfunction "OUT_2") (pintype "passive"))
      (node (ref "FB3") (pin "1") (pinfunction "OUT_1") (pintype "passive"))
      (node (ref "U2") (pin "3") (pinfunction "OUT_3") (pintype "passive"))
    )
    (net (code "55") (name "Net-(U3-D1)") (class "Default")
      (node (ref "T1") (pin "3") (pinfunction "1_3") (pintype "passive"))
      (node (ref "U3") (pin "1") (pinfunction "D1_1") (pintype "passive"))
    )
    (net (code "56") (name "Net-(U3-D2)") (class "Default")
      (node (ref "T1") (pin "1") (pinfunction "1_1") (pintype "passive"))
      (node (ref "U3") (pin "3") (pinfunction "D2_3") (pintype "passive"))
    )
    (net (code "57") (name "Net-(U4-FB)") (class "Default")
      (node (ref "C30") (pin "2") (pinfunction "OUT_2") (pintype "passive"))
      (node (ref "R25") (pin "1") (pinfunction "A_1") (pintype "passive"))
      (node (ref "R27") (pin "2") (pinfunction "A_2") (pintype "passive"))
      (node (ref "U4") (pin "2") (pinfunction "FB_2") (pintype "passive"))
    )
    (net (code "58") (name "Net-(U4-NR{slash}SS)") (class "Default")
      (node (ref "C34") (pin "2") (pinfunction "OUT_2") (pintype "passive"))
      (node (ref "U4") (pin "6") (pinfunction "NR/SS_6") (pintype "power_in"))
    )
    (net (code "59") (name "Net-(U4-OUT)") (class "Default")
      (node (ref "C30") (pin "1") (pinfunction "OUT_1") (pintype "passive"))
      (node (ref "C33") (pin "2") (pinfunction "OUT_2") (pintype "passive"))
      (node (ref "FB4") (pin "1") (pinfunction "OUT_1") (pintype "passive"))
      (node (ref "R25") (pin "2") (pinfunction "A_2") (pintype "passive"))
      (node (ref "U4") (pin "1") (pinfunction "OUT_1") (pintype "passive"))
    )
    (net (code "60") (name "Net-(U6-OUT)") (class "Default")
      (node (ref "C46") (pin "2") (pinfunction "OUT_2") (pintype "passive"))
      (node (ref "FB7") (pin "1") (pinfunction "OUT_1") (pintype "passive"))
      (node (ref "U6") (pin "3") (pinfunction "OUT_3") (pintype "passive"))
    )
    (net (code "61") (name "Net-(U7-D1)") (class "Default")
      (node (ref "T2") (pin "3") (pinfunction "1_3") (pintype "passive"))
      (node (ref "U7") (pin "1") (pinfunction "D1_1") (pintype "passive"))
    )
    (net (code "62") (name "Net-(U7-D2)") (class "Default")
      (node (ref "T2") (pin "1") (pinfunction "1_1") (pintype "passive"))
      (node (ref "U7") (pin "3") (pinfunction "D2_3") (pintype "passive"))
    )
    (net (code "63") (name "Net-(U8-FB)") (class "Default")
      (node (ref "C55") (pin "2") (pinfunction "OUT_2") (pintype "passive"))
      (node (ref "R16") (pin "1") (pinfunction "A_1") (pintype "passive"))
      (node (ref "R18") (pin "2") (pinfunction "A_2") (pintype "passive"))
      (node (ref "U8") (pin "2") (pinfunction "FB_2") (pintype "passive"))
    )
    (net (code "64") (name "Net-(U8-NR{slash}SS)") (class "Default")
      (node (ref "C59") (pin "2") (pinfunction "OUT_2") (pintype "passive"))
      (node (ref "U8") (pin "6") (pinfunction "NR/SS_6") (pintype "power_in"))
    )
    (net (code "65") (name "Net-(U8-OUT)") (class "Default")
      (node (ref "C55") (pin "1") (pinfunction "OUT_1") (pintype "passive"))
      (node (ref "C58") (pin "2") (pinfunction "OUT_2") (pintype "passive"))
      (node (ref "FB8") (pin "1") (pinfunction "OUT_1") (pintype "passive"))
      (node (ref "R16") (pin "2") (pinfunction "A_2") (pintype "passive"))
      (node (ref "U8") (pin "1") (pinfunction "OUT_1") (pintype "passive"))
    )
    (net (code "66") (name "Net-(U10-OUT)") (class "Default")
      (node (ref "C71") (pin "2") (pinfunction "OUT_2") (pintype "passive"))
      (node (ref "FB11") (pin "1") (pinfunction "OUT_1") (pintype "passive"))
      (node (ref "U10") (pin "3") (pinfunction "OUT_3") (pintype "passive"))
    )
    (net (code "67") (name "Net-(U11-D1)") (class "Default")
      (node (ref "T3") (pin "3") (pinfunction "1_3") (pintype "passive"))
      (node (ref "U11") (pin "1") (pinfunction "D1_1") (pintype "passive"))
    )
    (net (code "68") (name "Net-(U11-D2)") (class "Default")
      (node (ref "T3") (pin "1") (pinfunction "1_1") (pintype "passive"))
      (node (ref "U11") (pin "3") (pinfunction "D2_3") (pintype "passive"))
    )
    (net (code "69") (name "Net-(U12-FB)") (class "Default")
      (node (ref "C80") (pin "2") (pinfunction "OUT_2") (pintype "passive"))
      (node (ref "R34") (pin "1") (pinfunction "A_1") (pintype "passive"))
      (node (ref "R36") (pin "2") (pinfunction "A_2") (pintype "passive"))
      (node (ref "U12") (pin "2") (pinfunction "FB_2") (pintype "passive"))
    )
    (net (code "70") (name "Net-(U12-NR{slash}SS)") (class "Default")
      (node (ref "C84") (pin "2") (pinfunction "OUT_2") (pintype "passive"))
      (node (ref "U12") (pin "6") (pinfunction "NR/SS_6") (pintype "power_in"))
    )
    (net (code "71") (name "Net-(U12-OUT)") (class "Default")
      (node (ref "C80") (pin "1") (pinfunction "OUT_1") (pintype "passive"))
      (node (ref "C83") (pin "2") (pinfunction "OUT_2") (pintype "passive"))
      (node (ref "FB12") (pin "1") (pinfunction "OUT_1") (pintype "passive"))
      (node (ref "R34") (pin "2") (pinfunction "A_2") (pintype "passive"))
      (node (ref "U12") (pin "1") (pinfunction "OUT_1") (pintype "passive"))
    )
    (net (code "72") (name "unconnected-(T1-1-Pad5)") (class "Default")
      (node (ref "T1") (pin "5") (pinfunction "1_5") (pintype "passive"))
    )
    (net (code "73") (name "unconnected-(T2-1-Pad5)") (class "Default")
      (node (ref "T2") (pin "5") (pinfunction "1_5") (pintype "passive"))
    )
    (net (code "74") (name "unconnected-(T3-1-Pad5)") (class "Default")
      (node (ref "T3") (pin "5") (pinfunction "1_5") (pintype "passive"))
    )
    (net (code "75") (name "unconnected-(U2-NC-Pad4)") (class "Default")
      (node (ref "U2") (pin "4") (pinfunction "NC_4") (pintype "passive"))
    )
    (net (code "76") (name "unconnected-(U2-NC-Pad5)") (class "Default")
      (node (ref "U2") (pin "5") (pinfunction "NC_5") (pintype "passive"))
    )
    (net (code "77") (name "unconnected-(U4-DNC-Pad7)") (class "Default")
      (node (ref "U4") (pin "7") (pinfunction "DNC_7") (pintype "passive"))
    )
    (net (code "78") (name "unconnected-(U6-NC-Pad4)") (class "Default")
      (node (ref "U6") (pin "4") (pinfunction "NC_4") (pintype "passive"))
    )
    (net (code "79") (name "unconnected-(U6-NC-Pad5)") (class "Default")
      (node (ref "U6") (pin "5") (pinfunction "NC_5") (pintype "passive"))
    )
    (net (code "80") (name "unconnected-(U8-DNC-Pad7)") (class "Default")
      (node (ref "U8") (pin "7") (pinfunction "DNC_7") (pintype "passive"))
    )
    (net (code "81") (name "unconnected-(U10-NC-Pad4)") (class "Default")
      (node (ref "U10") (pin "4") (pinfunction "NC_4") (pintype "passive"))
    )
    (net (code "82") (name "unconnected-(U10-NC-Pad5)") (class "Default")
      (node (ref "U10") (pin "5") (pinfunction "NC_5") (pintype "passive"))
    )
    (net (code "83") (name "unconnected-(U12-DNC-Pad7)") (class "Default")
      (node (ref "U12") (pin "7") (pinfunction "DNC_7") (pintype "passive"))
    )
  )
)
